# SDRAM_DDR3_4x16.net
KiCad netlist of a schematic drawn in Altium Designer
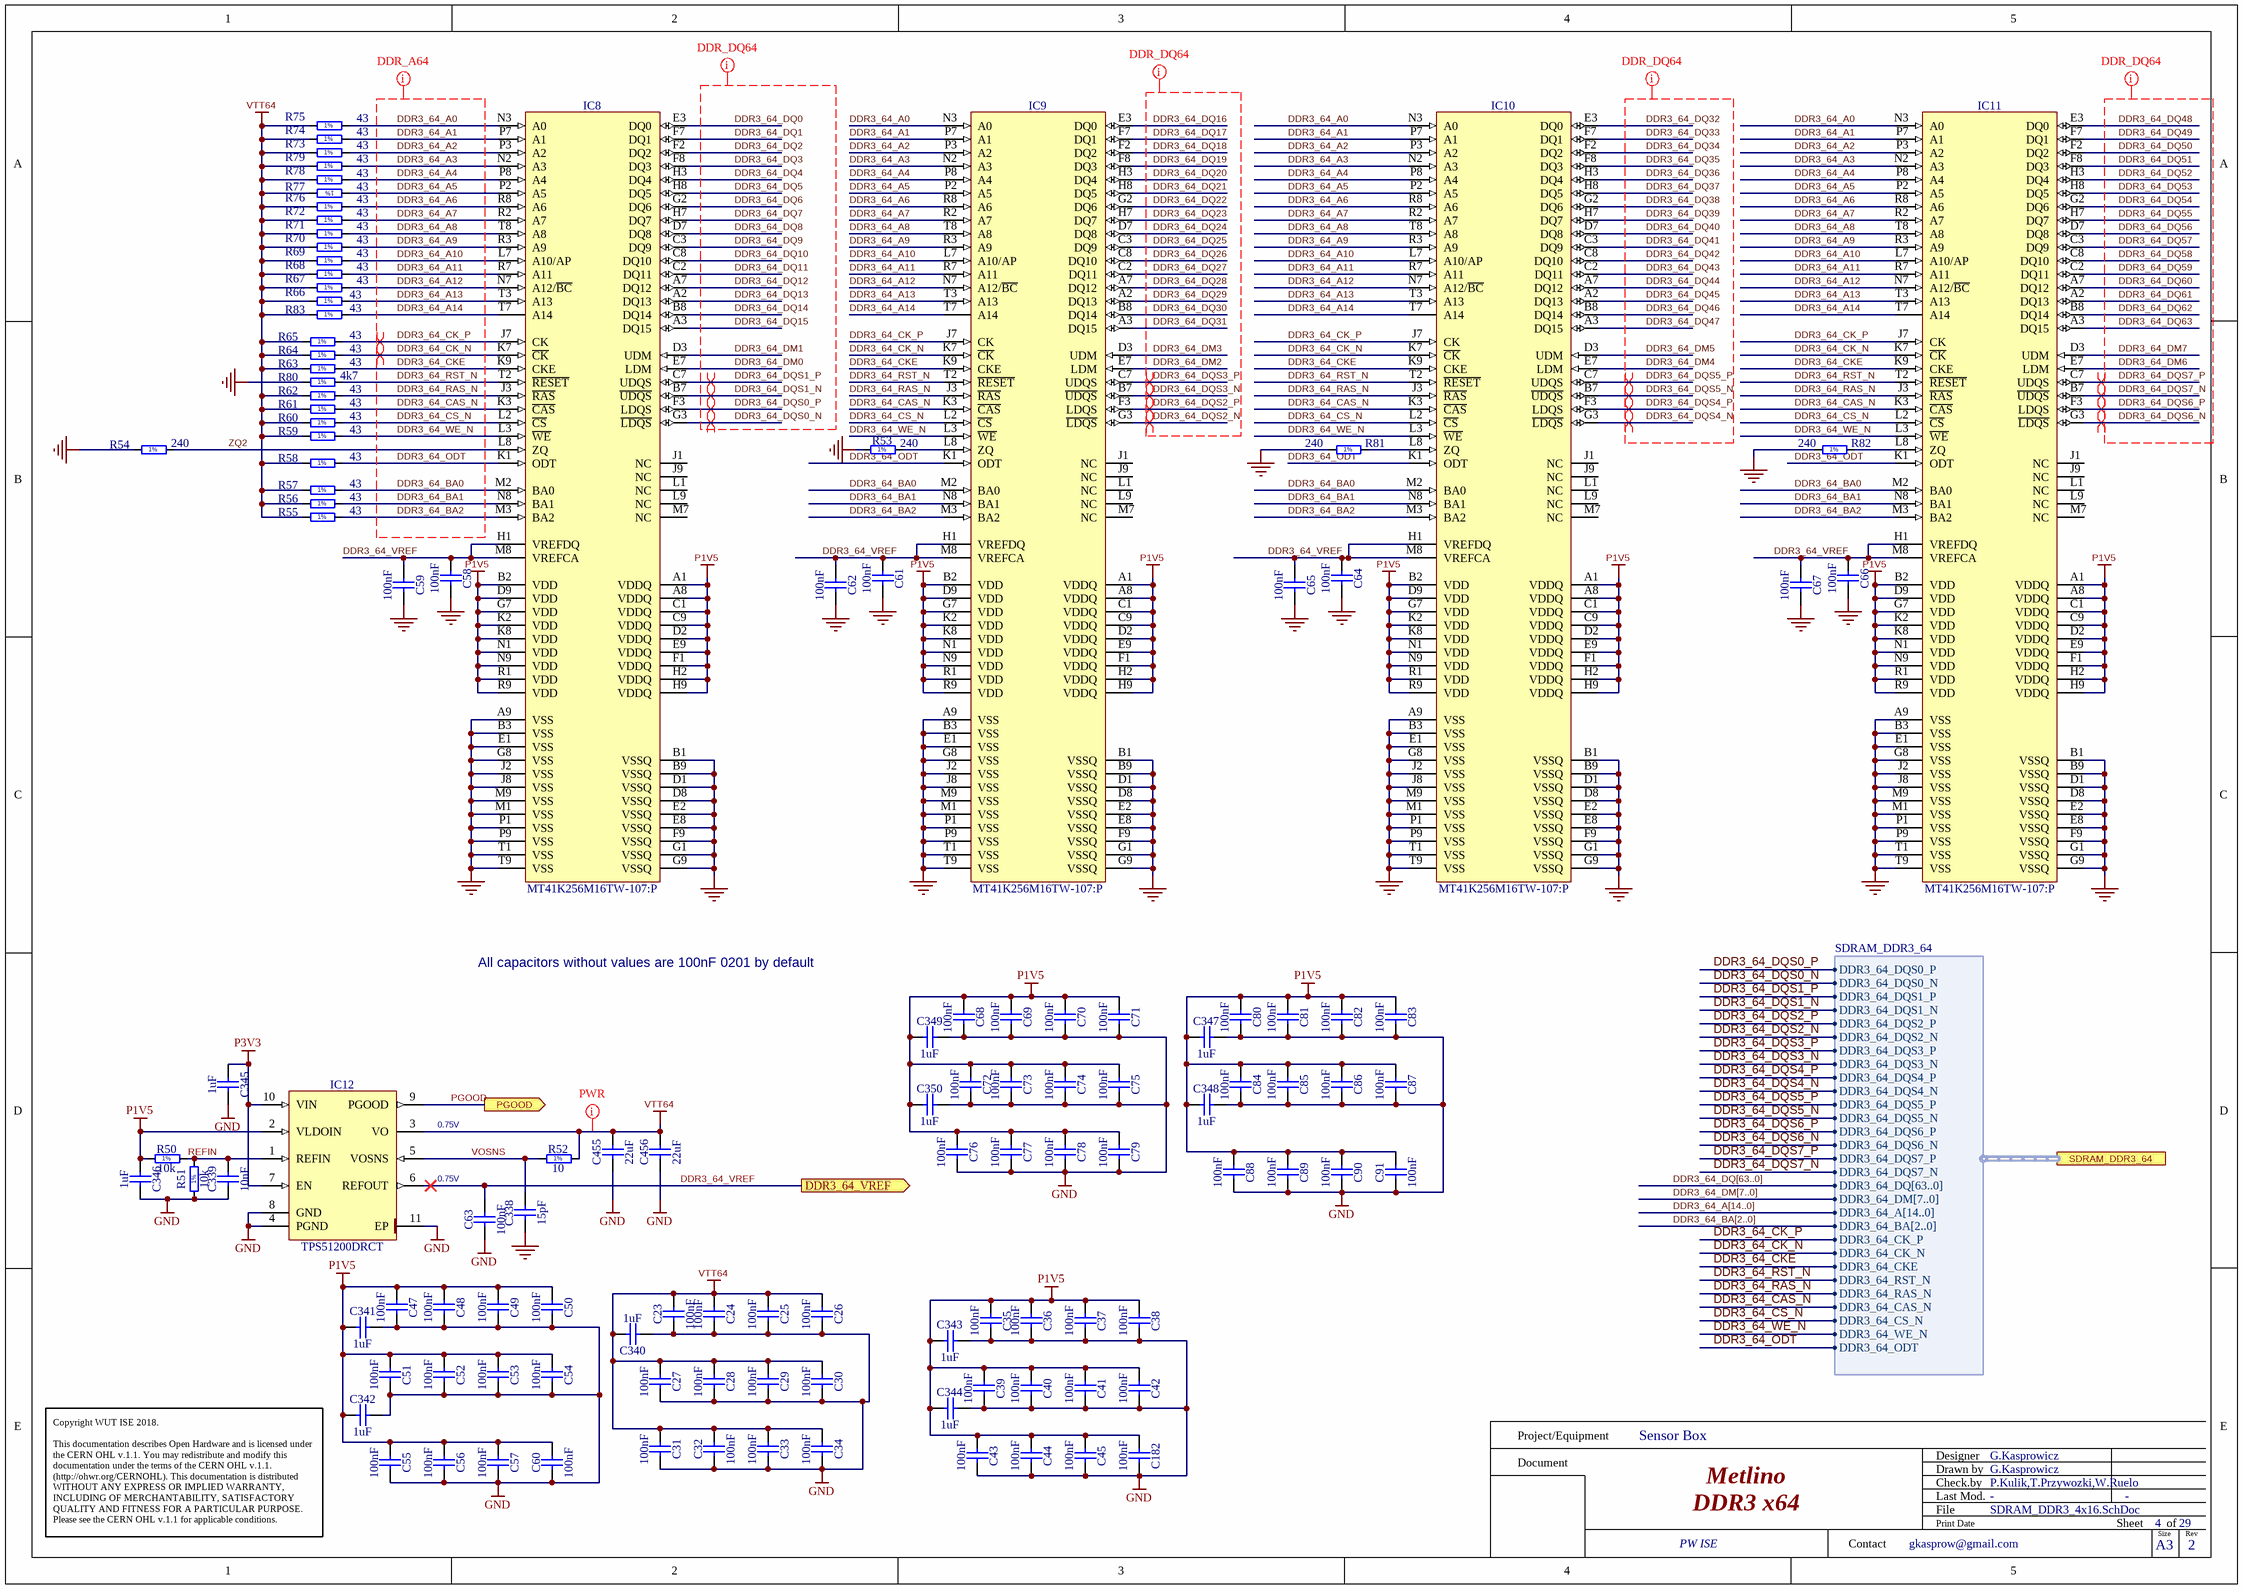
[diagram p0: SDRAM_DDR3_4x16.SchDoc]

(export (version "E")
  (design (tool "Eeschema 10.0.6"))
  (components
    (comp (ref "C23")
      (value "100nF")
      (footprint "CAPC0603X33N")
      (description "Non-polarised capacitor")
      (fields
        (field (name "MANUFACTURER PART NUMBER") "CC0201_100NF_6.3V_10%_X5R")
        (field (name "MANUFACTURER") "GENERIC")
        (field (name "AUTHOR") "CERN DEM JLC")
      )
      (libsource (lib "Capacitors") (part "Capacitor - non polarized"))
    )
    (comp (ref "C24")
      (value "100nF")
      (footprint "CAPC0603X33N")
      (description "Non-polarised capacitor")
      (fields
        (field (name "MANUFACTURER PART NUMBER") "CC0201_100NF_6.3V_10%_X5R")
        (field (name "MANUFACTURER") "GENERIC")
        (field (name "AUTHOR") "CERN DEM JLC")
      )
      (libsource (lib "Capacitors") (part "Capacitor - non polarized"))
    )
    (comp (ref "C25")
      (value "100nF")
      (footprint "CAPC0603X33N")
      (description "Non-polarised capacitor")
      (fields
        (field (name "MANUFACTURER PART NUMBER") "CC0201_100NF_6.3V_10%_X5R")
        (field (name "MANUFACTURER") "GENERIC")
        (field (name "AUTHOR") "CERN DEM JLC")
      )
      (libsource (lib "Capacitors") (part "Capacitor - non polarized"))
    )
    (comp (ref "C26")
      (value "100nF")
      (footprint "CAPC0603X33N")
      (description "Non-polarised capacitor")
      (fields
        (field (name "MANUFACTURER PART NUMBER") "CC0201_100NF_6.3V_10%_X5R")
        (field (name "MANUFACTURER") "GENERIC")
        (field (name "AUTHOR") "CERN DEM JLC")
      )
      (libsource (lib "Capacitors") (part "Capacitor - non polarized"))
    )
    (comp (ref "C27")
      (value "100nF")
      (footprint "CAPC0603X33N")
      (description "Non-polarised capacitor")
      (fields
        (field (name "MANUFACTURER PART NUMBER") "CC0201_100NF_6.3V_10%_X5R")
        (field (name "MANUFACTURER") "GENERIC")
        (field (name "AUTHOR") "CERN DEM JLC")
      )
      (libsource (lib "Capacitors") (part "Capacitor - non polarized"))
    )
    (comp (ref "C28")
      (value "100nF")
      (footprint "CAPC0603X33N")
      (description "Non-polarised capacitor")
      (fields
        (field (name "MANUFACTURER PART NUMBER") "CC0201_100NF_6.3V_10%_X5R")
        (field (name "MANUFACTURER") "GENERIC")
        (field (name "AUTHOR") "CERN DEM JLC")
      )
      (libsource (lib "Capacitors") (part "Capacitor - non polarized"))
    )
    (comp (ref "C29")
      (value "100nF")
      (footprint "CAPC0603X33N")
      (description "Non-polarised capacitor")
      (fields
        (field (name "MANUFACTURER PART NUMBER") "CC0201_100NF_6.3V_10%_X5R")
        (field (name "MANUFACTURER") "GENERIC")
        (field (name "AUTHOR") "CERN DEM JLC")
      )
      (libsource (lib "Capacitors") (part "Capacitor - non polarized"))
    )
    (comp (ref "C30")
      (value "100nF")
      (footprint "CAPC0603X33N")
      (description "Non-polarised capacitor")
      (fields
        (field (name "MANUFACTURER PART NUMBER") "CC0201_100NF_6.3V_10%_X5R")
        (field (name "MANUFACTURER") "GENERIC")
        (field (name "AUTHOR") "CERN DEM JLC")
      )
      (libsource (lib "Capacitors") (part "Capacitor - non polarized"))
    )
    (comp (ref "C31")
      (value "100nF")
      (footprint "CAPC0603X33N")
      (description "Non-polarised capacitor")
      (fields
        (field (name "MANUFACTURER PART NUMBER") "CC0201_100NF_6.3V_10%_X5R")
        (field (name "MANUFACTURER") "GENERIC")
        (field (name "AUTHOR") "CERN DEM JLC")
      )
      (libsource (lib "Capacitors") (part "Capacitor - non polarized"))
    )
    (comp (ref "C32")
      (value "100nF")
      (footprint "CAPC0603X33N")
      (description "Non-polarised capacitor")
      (fields
        (field (name "MANUFACTURER PART NUMBER") "CC0201_100NF_6.3V_10%_X5R")
        (field (name "MANUFACTURER") "GENERIC")
        (field (name "AUTHOR") "CERN DEM JLC")
      )
      (libsource (lib "Capacitors") (part "Capacitor - non polarized"))
    )
    (comp (ref "C33")
      (value "100nF")
      (footprint "CAPC0603X33N")
      (description "Non-polarised capacitor")
      (fields
        (field (name "MANUFACTURER PART NUMBER") "CC0201_100NF_6.3V_10%_X5R")
        (field (name "MANUFACTURER") "GENERIC")
        (field (name "AUTHOR") "CERN DEM JLC")
      )
      (libsource (lib "Capacitors") (part "Capacitor - non polarized"))
    )
    (comp (ref "C34")
      (value "100nF")
      (footprint "CAPC0603X33N")
      (description "Non-polarised capacitor")
      (fields
        (field (name "MANUFACTURER PART NUMBER") "CC0201_100NF_6.3V_10%_X5R")
        (field (name "MANUFACTURER") "GENERIC")
        (field (name "AUTHOR") "CERN DEM JLC")
      )
      (libsource (lib "Capacitors") (part "Capacitor - non polarized"))
    )
    (comp (ref "C35")
      (value "100nF")
      (footprint "CAPC0603X33N")
      (description "Non-polarised capacitor")
      (fields
        (field (name "MANUFACTURER PART NUMBER") "CC0201_100NF_6.3V_10%_X5R")
        (field (name "MANUFACTURER") "GENERIC")
        (field (name "AUTHOR") "CERN DEM JLC")
      )
      (libsource (lib "Capacitors") (part "Capacitor - non polarized"))
    )
    (comp (ref "C36")
      (value "100nF")
      (footprint "CAPC0603X33N")
      (description "Non-polarised capacitor")
      (fields
        (field (name "MANUFACTURER PART NUMBER") "CC0201_100NF_6.3V_10%_X5R")
        (field (name "MANUFACTURER") "GENERIC")
        (field (name "AUTHOR") "CERN DEM JLC")
      )
      (libsource (lib "Capacitors") (part "Capacitor - non polarized"))
    )
    (comp (ref "C37")
      (value "100nF")
      (footprint "CAPC0603X33N")
      (description "Non-polarised capacitor")
      (fields
        (field (name "MANUFACTURER PART NUMBER") "CC0201_100NF_6.3V_10%_X5R")
        (field (name "MANUFACTURER") "GENERIC")
        (field (name "AUTHOR") "CERN DEM JLC")
      )
      (libsource (lib "Capacitors") (part "Capacitor - non polarized"))
    )
    (comp (ref "C38")
      (value "100nF")
      (footprint "CAPC0603X33N")
      (description "Non-polarised capacitor")
      (fields
        (field (name "MANUFACTURER PART NUMBER") "CC0201_100NF_6.3V_10%_X5R")
        (field (name "MANUFACTURER") "GENERIC")
        (field (name "AUTHOR") "CERN DEM JLC")
      )
      (libsource (lib "Capacitors") (part "Capacitor - non polarized"))
    )
    (comp (ref "C39")
      (value "100nF")
      (footprint "CAPC0603X33N")
      (description "Non-polarised capacitor")
      (fields
        (field (name "MANUFACTURER PART NUMBER") "CC0201_100NF_6.3V_10%_X5R")
        (field (name "MANUFACTURER") "GENERIC")
        (field (name "AUTHOR") "CERN DEM JLC")
      )
      (libsource (lib "Capacitors") (part "Capacitor - non polarized"))
    )
    (comp (ref "C40")
      (value "100nF")
      (footprint "CAPC0603X33N")
      (description "Non-polarised capacitor")
      (fields
        (field (name "MANUFACTURER PART NUMBER") "CC0201_100NF_6.3V_10%_X5R")
        (field (name "MANUFACTURER") "GENERIC")
        (field (name "AUTHOR") "CERN DEM JLC")
      )
      (libsource (lib "Capacitors") (part "Capacitor - non polarized"))
    )
    (comp (ref "C41")
      (value "100nF")
      (footprint "CAPC0603X33N")
      (description "Non-polarised capacitor")
      (fields
        (field (name "MANUFACTURER PART NUMBER") "CC0201_100NF_6.3V_10%_X5R")
        (field (name "MANUFACTURER") "GENERIC")
        (field (name "AUTHOR") "CERN DEM JLC")
      )
      (libsource (lib "Capacitors") (part "Capacitor - non polarized"))
    )
    (comp (ref "C42")
      (value "100nF")
      (footprint "CAPC0603X33N")
      (description "Non-polarised capacitor")
      (fields
        (field (name "MANUFACTURER PART NUMBER") "CC0201_100NF_6.3V_10%_X5R")
        (field (name "MANUFACTURER") "GENERIC")
        (field (name "AUTHOR") "CERN DEM JLC")
      )
      (libsource (lib "Capacitors") (part "Capacitor - non polarized"))
    )
    (comp (ref "C43")
      (value "100nF")
      (footprint "CAPC0603X33N")
      (description "Non-polarised capacitor")
      (fields
        (field (name "MANUFACTURER PART NUMBER") "CC0201_100NF_6.3V_10%_X5R")
        (field (name "MANUFACTURER") "GENERIC")
        (field (name "AUTHOR") "CERN DEM JLC")
      )
      (libsource (lib "Capacitors") (part "Capacitor - non polarized"))
    )
    (comp (ref "C44")
      (value "100nF")
      (footprint "CAPC0603X33N")
      (description "Non-polarised capacitor")
      (fields
        (field (name "MANUFACTURER PART NUMBER") "CC0201_100NF_6.3V_10%_X5R")
        (field (name "MANUFACTURER") "GENERIC")
        (field (name "AUTHOR") "CERN DEM JLC")
      )
      (libsource (lib "Capacitors") (part "Capacitor - non polarized"))
    )
    (comp (ref "C45")
      (value "100nF")
      (footprint "CAPC0603X33N")
      (description "Non-polarised capacitor")
      (fields
        (field (name "MANUFACTURER PART NUMBER") "CC0201_100NF_6.3V_10%_X5R")
        (field (name "MANUFACTURER") "GENERIC")
        (field (name "AUTHOR") "CERN DEM JLC")
      )
      (libsource (lib "Capacitors") (part "Capacitor - non polarized"))
    )
    (comp (ref "C47")
      (value "100nF")
      (footprint "CAPC0603X33N")
      (description "Non-polarised capacitor")
      (fields
        (field (name "MANUFACTURER PART NUMBER") "CC0201_100NF_6.3V_10%_X5R")
        (field (name "MANUFACTURER") "GENERIC")
        (field (name "AUTHOR") "CERN DEM JLC")
      )
      (libsource (lib "Capacitors") (part "Capacitor - non polarized"))
    )
    (comp (ref "C48")
      (value "100nF")
      (footprint "CAPC0603X33N")
      (description "Non-polarised capacitor")
      (fields
        (field (name "MANUFACTURER PART NUMBER") "CC0201_100NF_6.3V_10%_X5R")
        (field (name "MANUFACTURER") "GENERIC")
        (field (name "AUTHOR") "CERN DEM JLC")
      )
      (libsource (lib "Capacitors") (part "Capacitor - non polarized"))
    )
    (comp (ref "C49")
      (value "100nF")
      (footprint "CAPC0603X33N")
      (description "Non-polarised capacitor")
      (fields
        (field (name "MANUFACTURER PART NUMBER") "CC0201_100NF_6.3V_10%_X5R")
        (field (name "MANUFACTURER") "GENERIC")
        (field (name "AUTHOR") "CERN DEM JLC")
      )
      (libsource (lib "Capacitors") (part "Capacitor - non polarized"))
    )
    (comp (ref "C50")
      (value "100nF")
      (footprint "CAPC0603X33N")
      (description "Non-polarised capacitor")
      (fields
        (field (name "MANUFACTURER PART NUMBER") "CC0201_100NF_6.3V_10%_X5R")
        (field (name "MANUFACTURER") "GENERIC")
        (field (name "AUTHOR") "CERN DEM JLC")
      )
      (libsource (lib "Capacitors") (part "Capacitor - non polarized"))
    )
    (comp (ref "C51")
      (value "100nF")
      (footprint "CAPC0603X33N")
      (description "Non-polarised capacitor")
      (fields
        (field (name "MANUFACTURER PART NUMBER") "CC0201_100NF_6.3V_10%_X5R")
        (field (name "MANUFACTURER") "GENERIC")
        (field (name "AUTHOR") "CERN DEM JLC")
      )
      (libsource (lib "Capacitors") (part "Capacitor - non polarized"))
    )
    (comp (ref "C52")
      (value "100nF")
      (footprint "CAPC0603X33N")
      (description "Non-polarised capacitor")
      (fields
        (field (name "MANUFACTURER PART NUMBER") "CC0201_100NF_6.3V_10%_X5R")
        (field (name "MANUFACTURER") "GENERIC")
        (field (name "AUTHOR") "CERN DEM JLC")
      )
      (libsource (lib "Capacitors") (part "Capacitor - non polarized"))
    )
    (comp (ref "C53")
      (value "100nF")
      (footprint "CAPC0603X33N")
      (description "Non-polarised capacitor")
      (fields
        (field (name "MANUFACTURER PART NUMBER") "CC0201_100NF_6.3V_10%_X5R")
        (field (name "MANUFACTURER") "GENERIC")
        (field (name "AUTHOR") "CERN DEM JLC")
      )
      (libsource (lib "Capacitors") (part "Capacitor - non polarized"))
    )
    (comp (ref "C54")
      (value "100nF")
      (footprint "CAPC0603X33N")
      (description "Non-polarised capacitor")
      (fields
        (field (name "MANUFACTURER PART NUMBER") "CC0201_100NF_6.3V_10%_X5R")
        (field (name "MANUFACTURER") "GENERIC")
        (field (name "AUTHOR") "CERN DEM JLC")
      )
      (libsource (lib "Capacitors") (part "Capacitor - non polarized"))
    )
    (comp (ref "C55")
      (value "100nF")
      (footprint "CAPC0603X33N")
      (description "Non-polarised capacitor")
      (fields
        (field (name "MANUFACTURER PART NUMBER") "CC0201_100NF_6.3V_10%_X5R")
        (field (name "MANUFACTURER") "GENERIC")
        (field (name "AUTHOR") "CERN DEM JLC")
      )
      (libsource (lib "Capacitors") (part "Capacitor - non polarized"))
    )
    (comp (ref "C56")
      (value "100nF")
      (footprint "CAPC0603X33N")
      (description "Non-polarised capacitor")
      (fields
        (field (name "MANUFACTURER PART NUMBER") "CC0201_100NF_6.3V_10%_X5R")
        (field (name "MANUFACTURER") "GENERIC")
        (field (name "AUTHOR") "CERN DEM JLC")
      )
      (libsource (lib "Capacitors") (part "Capacitor - non polarized"))
    )
    (comp (ref "C57")
      (value "100nF")
      (footprint "CAPC0603X33N")
      (description "Non-polarised capacitor")
      (fields
        (field (name "MANUFACTURER PART NUMBER") "CC0201_100NF_6.3V_10%_X5R")
        (field (name "MANUFACTURER") "GENERIC")
        (field (name "AUTHOR") "CERN DEM JLC")
      )
      (libsource (lib "Capacitors") (part "Capacitor - non polarized"))
    )
    (comp (ref "C58")
      (value "100nF")
      (footprint "CAPC0603X33N")
      (description "Non-polarised capacitor")
      (fields
        (field (name "MANUFACTURER PART NUMBER") "CC0201_100NF_6.3V_10%_X5R")
        (field (name "MANUFACTURER") "GENERIC")
        (field (name "AUTHOR") "CERN DEM JLC")
      )
      (libsource (lib "Capacitors") (part "Capacitor - non polarized"))
    )
    (comp (ref "C59")
      (value "100nF")
      (footprint "CAPC0603X33N")
      (description "Non-polarised capacitor")
      (fields
        (field (name "MANUFACTURER PART NUMBER") "CC0201_100NF_6.3V_10%_X5R")
        (field (name "MANUFACTURER") "GENERIC")
        (field (name "AUTHOR") "CERN DEM JLC")
      )
      (libsource (lib "Capacitors") (part "Capacitor - non polarized"))
    )
    (comp (ref "C60")
      (value "100nF")
      (footprint "CAPC0603X33N")
      (description "Non-polarised capacitor")
      (fields
        (field (name "MANUFACTURER PART NUMBER") "CC0201_100NF_6.3V_10%_X5R")
        (field (name "MANUFACTURER") "GENERIC")
        (field (name "AUTHOR") "CERN DEM JLC")
      )
      (libsource (lib "Capacitors") (part "Capacitor - non polarized"))
    )
    (comp (ref "C61")
      (value "100nF")
      (footprint "CAPC0603X33N")
      (description "Non-polarised capacitor")
      (fields
        (field (name "MANUFACTURER PART NUMBER") "CC0201_100NF_6.3V_10%_X5R")
        (field (name "MANUFACTURER") "GENERIC")
        (field (name "AUTHOR") "CERN DEM JLC")
      )
      (libsource (lib "Capacitors") (part "Capacitor - non polarized"))
    )
    (comp (ref "C62")
      (value "100nF")
      (footprint "CAPC0603X33N")
      (description "Non-polarised capacitor")
      (fields
        (field (name "MANUFACTURER PART NUMBER") "CC0201_100NF_6.3V_10%_X5R")
        (field (name "MANUFACTURER") "GENERIC")
        (field (name "AUTHOR") "CERN DEM JLC")
      )
      (libsource (lib "Capacitors") (part "Capacitor - non polarized"))
    )
    (comp (ref "C63")
      (value "100nF")
      (footprint "CAPC0603X33N")
      (description "Non-polarised capacitor")
      (fields
        (field (name "MANUFACTURER PART NUMBER") "CC0201_100NF_6.3V_10%_X5R")
        (field (name "MANUFACTURER") "GENERIC")
        (field (name "AUTHOR") "CERN DEM JLC")
      )
      (libsource (lib "Capacitors") (part "Capacitor - non polarized"))
    )
    (comp (ref "C64")
      (value "100nF")
      (footprint "CAPC0603X33N")
      (description "Non-polarised capacitor")
      (fields
        (field (name "MANUFACTURER PART NUMBER") "CC0201_100NF_6.3V_10%_X5R")
        (field (name "MANUFACTURER") "GENERIC")
        (field (name "AUTHOR") "CERN DEM JLC")
      )
      (libsource (lib "Capacitors") (part "Capacitor - non polarized"))
    )
    (comp (ref "C65")
      (value "100nF")
      (footprint "CAPC0603X33N")
      (description "Non-polarised capacitor")
      (fields
        (field (name "MANUFACTURER PART NUMBER") "CC0201_100NF_6.3V_10%_X5R")
        (field (name "MANUFACTURER") "GENERIC")
        (field (name "AUTHOR") "CERN DEM JLC")
      )
      (libsource (lib "Capacitors") (part "Capacitor - non polarized"))
    )
    (comp (ref "C66")
      (value "100nF")
      (footprint "CAPC0603X33N")
      (description "Non-polarised capacitor")
      (fields
        (field (name "MANUFACTURER PART NUMBER") "CC0201_100NF_6.3V_10%_X5R")
        (field (name "MANUFACTURER") "GENERIC")
        (field (name "AUTHOR") "CERN DEM JLC")
      )
      (libsource (lib "Capacitors") (part "Capacitor - non polarized"))
    )
    (comp (ref "C67")
      (value "100nF")
      (footprint "CAPC0603X33N")
      (description "Non-polarised capacitor")
      (fields
        (field (name "MANUFACTURER PART NUMBER") "CC0201_100NF_6.3V_10%_X5R")
        (field (name "MANUFACTURER") "GENERIC")
        (field (name "AUTHOR") "CERN DEM JLC")
      )
      (libsource (lib "Capacitors") (part "Capacitor - non polarized"))
    )
    (comp (ref "C68")
      (value "100nF")
      (footprint "CAPC0603X33N")
      (description "Non-polarised capacitor")
      (fields
        (field (name "MANUFACTURER PART NUMBER") "CC0201_100NF_6.3V_10%_X5R")
        (field (name "MANUFACTURER") "GENERIC")
        (field (name "AUTHOR") "CERN DEM JLC")
      )
      (libsource (lib "Capacitors") (part "Capacitor - non polarized"))
    )
    (comp (ref "C69")
      (value "100nF")
      (footprint "CAPC0603X33N")
      (description "Non-polarised capacitor")
      (fields
        (field (name "MANUFACTURER PART NUMBER") "CC0201_100NF_6.3V_10%_X5R")
        (field (name "MANUFACTURER") "GENERIC")
        (field (name "AUTHOR") "CERN DEM JLC")
      )
      (libsource (lib "Capacitors") (part "Capacitor - non polarized"))
    )
    (comp (ref "C70")
      (value "100nF")
      (footprint "CAPC0603X33N")
      (description "Non-polarised capacitor")
      (fields
        (field (name "MANUFACTURER PART NUMBER") "CC0201_100NF_6.3V_10%_X5R")
        (field (name "MANUFACTURER") "GENERIC")
        (field (name "AUTHOR") "CERN DEM JLC")
      )
      (libsource (lib "Capacitors") (part "Capacitor - non polarized"))
    )
    (comp (ref "C71")
      (value "100nF")
      (footprint "CAPC0603X33N")
      (description "Non-polarised capacitor")
      (fields
        (field (name "MANUFACTURER PART NUMBER") "CC0201_100NF_6.3V_10%_X5R")
        (field (name "MANUFACTURER") "GENERIC")
        (field (name "AUTHOR") "CERN DEM JLC")
      )
      (libsource (lib "Capacitors") (part "Capacitor - non polarized"))
    )
    (comp (ref "C72")
      (value "100nF")
      (footprint "CAPC0603X33N")
      (description "Non-polarised capacitor")
      (fields
        (field (name "MANUFACTURER PART NUMBER") "CC0201_100NF_6.3V_10%_X5R")
        (field (name "MANUFACTURER") "GENERIC")
        (field (name "AUTHOR") "CERN DEM JLC")
      )
      (libsource (lib "Capacitors") (part "Capacitor - non polarized"))
    )
    (comp (ref "C73")
      (value "100nF")
      (footprint "CAPC0603X33N")
      (description "Non-polarised capacitor")
      (fields
        (field (name "MANUFACTURER PART NUMBER") "CC0201_100NF_6.3V_10%_X5R")
        (field (name "MANUFACTURER") "GENERIC")
        (field (name "AUTHOR") "CERN DEM JLC")
      )
      (libsource (lib "Capacitors") (part "Capacitor - non polarized"))
    )
    (comp (ref "C74")
      (value "100nF")
      (footprint "CAPC0603X33N")
      (description "Non-polarised capacitor")
      (fields
        (field (name "MANUFACTURER PART NUMBER") "CC0201_100NF_6.3V_10%_X5R")
        (field (name "MANUFACTURER") "GENERIC")
        (field (name "AUTHOR") "CERN DEM JLC")
      )
      (libsource (lib "Capacitors") (part "Capacitor - non polarized"))
    )
    (comp (ref "C75")
      (value "100nF")
      (footprint "CAPC0603X33N")
      (description "Non-polarised capacitor")
      (fields
        (field (name "MANUFACTURER PART NUMBER") "CC0201_100NF_6.3V_10%_X5R")
        (field (name "MANUFACTURER") "GENERIC")
        (field (name "AUTHOR") "CERN DEM JLC")
      )
      (libsource (lib "Capacitors") (part "Capacitor - non polarized"))
    )
    (comp (ref "C76")
      (value "100nF")
      (footprint "CAPC0603X33N")
      (description "Non-polarised capacitor")
      (fields
        (field (name "MANUFACTURER PART NUMBER") "CC0201_100NF_6.3V_10%_X5R")
        (field (name "MANUFACTURER") "GENERIC")
        (field (name "AUTHOR") "CERN DEM JLC")
      )
      (libsource (lib "Capacitors") (part "Capacitor - non polarized"))
    )
    (comp (ref "C77")
      (value "100nF")
      (footprint "CAPC0603X33N")
      (description "Non-polarised capacitor")
      (fields
        (field (name "MANUFACTURER PART NUMBER") "CC0201_100NF_6.3V_10%_X5R")
        (field (name "MANUFACTURER") "GENERIC")
        (field (name "AUTHOR") "CERN DEM JLC")
      )
      (libsource (lib "Capacitors") (part "Capacitor - non polarized"))
    )
    (comp (ref "C78")
      (value "100nF")
      (footprint "CAPC0603X33N")
      (description "Non-polarised capacitor")
      (fields
        (field (name "MANUFACTURER PART NUMBER") "CC0201_100NF_6.3V_10%_X5R")
        (field (name "MANUFACTURER") "GENERIC")
        (field (name "AUTHOR") "CERN DEM JLC")
      )
      (libsource (lib "Capacitors") (part "Capacitor - non polarized"))
    )
    (comp (ref "C79")
      (value "100nF")
      (footprint "CAPC0603X33N")
      (description "Non-polarised capacitor")
      (fields
        (field (name "MANUFACTURER PART NUMBER") "CC0201_100NF_6.3V_10%_X5R")
        (field (name "MANUFACTURER") "GENERIC")
        (field (name "AUTHOR") "CERN DEM JLC")
      )
      (libsource (lib "Capacitors") (part "Capacitor - non polarized"))
    )
    (comp (ref "C80")
      (value "100nF")
      (footprint "CAPC0603X33N")
      (description "Non-polarised capacitor")
      (fields
        (field (name "MANUFACTURER PART NUMBER") "CC0201_100NF_6.3V_10%_X5R")
        (field (name "MANUFACTURER") "GENERIC")
        (field (name "AUTHOR") "CERN DEM JLC")
      )
      (libsource (lib "Capacitors") (part "Capacitor - non polarized"))
    )
    (comp (ref "C81")
      (value "100nF")
      (footprint "CAPC0603X33N")
      (description "Non-polarised capacitor")
      (fields
        (field (name "MANUFACTURER PART NUMBER") "CC0201_100NF_6.3V_10%_X5R")
        (field (name "MANUFACTURER") "GENERIC")
        (field (name "AUTHOR") "CERN DEM JLC")
      )
      (libsource (lib "Capacitors") (part "Capacitor - non polarized"))
    )
    (comp (ref "C82")
      (value "100nF")
      (footprint "CAPC0603X33N")
      (description "Non-polarised capacitor")
      (fields
        (field (name "MANUFACTURER PART NUMBER") "CC0201_100NF_6.3V_10%_X5R")
        (field (name "MANUFACTURER") "GENERIC")
        (field (name "AUTHOR") "CERN DEM JLC")
      )
      (libsource (lib "Capacitors") (part "Capacitor - non polarized"))
    )
    (comp (ref "C83")
      (value "100nF")
      (footprint "CAPC0603X33N")
      (description "Non-polarised capacitor")
      (fields
        (field (name "MANUFACTURER PART NUMBER") "CC0201_100NF_6.3V_10%_X5R")
        (field (name "MANUFACTURER") "GENERIC")
        (field (name "AUTHOR") "CERN DEM JLC")
      )
      (libsource (lib "Capacitors") (part "Capacitor - non polarized"))
    )
    (comp (ref "C84")
      (value "100nF")
      (footprint "CAPC0603X33N")
      (description "Non-polarised capacitor")
      (fields
        (field (name "MANUFACTURER PART NUMBER") "CC0201_100NF_6.3V_10%_X5R")
        (field (name "MANUFACTURER") "GENERIC")
        (field (name "AUTHOR") "CERN DEM JLC")
      )
      (libsource (lib "Capacitors") (part "Capacitor - non polarized"))
    )
    (comp (ref "C85")
      (value "100nF")
      (footprint "CAPC0603X33N")
      (description "Non-polarised capacitor")
      (fields
        (field (name "MANUFACTURER PART NUMBER") "CC0201_100NF_6.3V_10%_X5R")
        (field (name "MANUFACTURER") "GENERIC")
        (field (name "AUTHOR") "CERN DEM JLC")
      )
      (libsource (lib "Capacitors") (part "Capacitor - non polarized"))
    )
    (comp (ref "C86")
      (value "100nF")
      (footprint "CAPC0603X33N")
      (description "Non-polarised capacitor")
      (fields
        (field (name "MANUFACTURER PART NUMBER") "CC0201_100NF_6.3V_10%_X5R")
        (field (name "MANUFACTURER") "GENERIC")
        (field (name "AUTHOR") "CERN DEM JLC")
      )
      (libsource (lib "Capacitors") (part "Capacitor - non polarized"))
    )
    (comp (ref "C87")
      (value "100nF")
      (footprint "CAPC0603X33N")
      (description "Non-polarised capacitor")
      (fields
        (field (name "MANUFACTURER PART NUMBER") "CC0201_100NF_6.3V_10%_X5R")
        (field (name "MANUFACTURER") "GENERIC")
        (field (name "AUTHOR") "CERN DEM JLC")
      )
      (libsource (lib "Capacitors") (part "Capacitor - non polarized"))
    )
    (comp (ref "C88")
      (value "100nF")
      (footprint "CAPC0603X33N")
      (description "Non-polarised capacitor")
      (fields
        (field (name "MANUFACTURER PART NUMBER") "CC0201_100NF_6.3V_10%_X5R")
        (field (name "MANUFACTURER") "GENERIC")
        (field (name "AUTHOR") "CERN DEM JLC")
      )
      (libsource (lib "Capacitors") (part "Capacitor - non polarized"))
    )
    (comp (ref "C89")
      (value "100nF")
      (footprint "CAPC0603X33N")
      (description "Non-polarised capacitor")
      (fields
        (field (name "MANUFACTURER PART NUMBER") "CC0201_100NF_6.3V_10%_X5R")
        (field (name "MANUFACTURER") "GENERIC")
        (field (name "AUTHOR") "CERN DEM JLC")
      )
      (libsource (lib "Capacitors") (part "Capacitor - non polarized"))
    )
    (comp (ref "C90")
      (value "100nF")
      (footprint "CAPC0603X33N")
      (description "Non-polarised capacitor")
      (fields
        (field (name "MANUFACTURER PART NUMBER") "CC0201_100NF_6.3V_10%_X5R")
        (field (name "MANUFACTURER") "GENERIC")
        (field (name "AUTHOR") "CERN DEM JLC")
      )
      (libsource (lib "Capacitors") (part "Capacitor - non polarized"))
    )
    (comp (ref "C91")
      (value "100nF")
      (footprint "CAPC0603X33N")
      (description "Non-polarised capacitor")
      (fields
        (field (name "MANUFACTURER PART NUMBER") "CC0201_100NF_6.3V_10%_X5R")
        (field (name "MANUFACTURER") "GENERIC")
        (field (name "AUTHOR") "CERN DEM JLC")
      )
      (libsource (lib "Capacitors") (part "Capacitor - non polarized"))
    )
    (comp (ref "C182")
      (value "100nF")
      (footprint "CAPC0603X33N")
      (description "Non-polarised capacitor")
      (fields
        (field (name "MANUFACTURER PART NUMBER") "CC0201_100NF_6.3V_10%_X5R")
        (field (name "MANUFACTURER") "GENERIC")
        (field (name "AUTHOR") "CERN DEM JLC")
      )
      (libsource (lib "Capacitors") (part "Capacitor - non polarized"))
    )
    (comp (ref "C338")
      (value "15pF")
      (footprint "CAPC1005X55N")
      (description "Non-polarised capacitor")
      (fields
        (field (name "MANUFACTURER PART NUMBER") "CC0402_15PF_50V_5%_C0G")
        (field (name "MANUFACTURER") "GENERIC")
        (field (name "AUTHOR") "CERN DEM JLC")
      )
      (libsource (lib "Capacitors") (part "Capacitor - non polarized"))
    )
    (comp (ref "C339")
      (value "10nF")
      (footprint "CAPC1005X55N")
      (description "Non-polarised capacitor")
      (fields
        (field (name "MANUFACTURER PART NUMBER") "CC0402_10NF_25V_10%_X7R")
        (field (name "MANUFACTURER") "GENERIC")
        (field (name "AUTHOR") "CERN DEM JLC")
      )
      (libsource (lib "Capacitors") (part "Capacitor - non polarized"))
    )
    (comp (ref "C340")
      (value "1uF")
      (footprint "CAPC1005X55N")
      (description "Non-polarised capacitor")
      (fields
        (field (name "MANUFACTURER PART NUMBER") "CC0402_1UF_16V_10%_X5R")
        (field (name "MANUFACTURER") "GENERIC")
        (field (name "AUTHOR") "CERN DEM JLC")
      )
      (libsource (lib "Capacitors") (part "Capacitor - non polarized"))
    )
    (comp (ref "C341")
      (value "1uF")
      (footprint "CAPC1005X55N")
      (description "Non-polarised capacitor")
      (fields
        (field (name "MANUFACTURER PART NUMBER") "CC0402_1UF_16V_10%_X5R")
        (field (name "MANUFACTURER") "GENERIC")
        (field (name "AUTHOR") "CERN DEM JLC")
      )
      (libsource (lib "Capacitors") (part "Capacitor - non polarized"))
    )
    (comp (ref "C342")
      (value "1uF")
      (footprint "CAPC1005X55N")
      (description "Non-polarised capacitor")
      (fields
        (field (name "MANUFACTURER PART NUMBER") "CC0402_1UF_16V_10%_X5R")
        (field (name "MANUFACTURER") "GENERIC")
        (field (name "AUTHOR") "CERN DEM JLC")
      )
      (libsource (lib "Capacitors") (part "Capacitor - non polarized"))
    )
    (comp (ref "C343")
      (value "1uF")
      (footprint "CAPC1005X55N")
      (description "Non-polarised capacitor")
      (fields
        (field (name "MANUFACTURER PART NUMBER") "CC0402_1UF_16V_10%_X5R")
        (field (name "MANUFACTURER") "GENERIC")
        (field (name "AUTHOR") "CERN DEM JLC")
      )
      (libsource (lib "Capacitors") (part "Capacitor - non polarized"))
    )
    (comp (ref "C344")
      (value "1uF")
      (footprint "CAPC1005X55N")
      (description "Non-polarised capacitor")
      (fields
        (field (name "MANUFACTURER PART NUMBER") "CC0402_1UF_16V_10%_X5R")
        (field (name "MANUFACTURER") "GENERIC")
        (field (name "AUTHOR") "CERN DEM JLC")
      )
      (libsource (lib "Capacitors") (part "Capacitor - non polarized"))
    )
    (comp (ref "C345")
      (value "1uF")
      (footprint "CAPC1005X55N")
      (description "Non-polarised capacitor")
      (fields
        (field (name "MANUFACTURER PART NUMBER") "CC0402_1UF_16V_10%_X5R")
        (field (name "MANUFACTURER") "GENERIC")
        (field (name "AUTHOR") "CERN DEM JLC")
      )
      (libsource (lib "Capacitors") (part "Capacitor - non polarized"))
    )
    (comp (ref "C346")
      (value "1uF")
      (footprint "CAPC1005X55N")
      (description "Non-polarised capacitor")
      (fields
        (field (name "MANUFACTURER PART NUMBER") "CC0402_1UF_16V_10%_X5R")
        (field (name "MANUFACTURER") "GENERIC")
        (field (name "AUTHOR") "CERN DEM JLC")
      )
      (libsource (lib "Capacitors") (part "Capacitor - non polarized"))
    )
    (comp (ref "C347")
      (value "1uF")
      (footprint "CAPC1005X55N")
      (description "Non-polarised capacitor")
      (fields
        (field (name "MANUFACTURER PART NUMBER") "CC0402_1UF_16V_10%_X5R")
        (field (name "MANUFACTURER") "GENERIC")
        (field (name "AUTHOR") "CERN DEM JLC")
      )
      (libsource (lib "Capacitors") (part "Capacitor - non polarized"))
    )
    (comp (ref "C348")
      (value "1uF")
      (footprint "CAPC1005X55N")
      (description "Non-polarised capacitor")
      (fields
        (field (name "MANUFACTURER PART NUMBER") "CC0402_1UF_16V_10%_X5R")
        (field (name "MANUFACTURER") "GENERIC")
        (field (name "AUTHOR") "CERN DEM JLC")
      )
      (libsource (lib "Capacitors") (part "Capacitor - non polarized"))
    )
    (comp (ref "C349")
      (value "1uF")
      (footprint "CAPC1005X55N")
      (description "Non-polarised capacitor")
      (fields
        (field (name "MANUFACTURER PART NUMBER") "CC0402_1UF_16V_10%_X5R")
        (field (name "MANUFACTURER") "GENERIC")
        (field (name "AUTHOR") "CERN DEM JLC")
      )
      (libsource (lib "Capacitors") (part "Capacitor - non polarized"))
    )
    (comp (ref "C350")
      (value "1uF")
      (footprint "CAPC1005X55N")
      (description "Non-polarised capacitor")
      (fields
        (field (name "MANUFACTURER PART NUMBER") "CC0402_1UF_16V_10%_X5R")
        (field (name "MANUFACTURER") "GENERIC")
        (field (name "AUTHOR") "CERN DEM JLC")
      )
      (libsource (lib "Capacitors") (part "Capacitor - non polarized"))
    )
    (comp (ref "C455")
      (value "22uF")
      (footprint "CAPC2012X135N")
      (description "Non-polarised capacitor")
      (fields
        (field (name "MANUFACTURER PART NUMBER") "CC0805_22UF_10V_+80%-20%_Y5V")
        (field (name "MANUFACTURER") "GENERIC")
        (field (name "AUTHOR") "CERN DEM JLC")
      )
      (libsource (lib "Capacitors") (part "Capacitor - non polarized"))
    )
    (comp (ref "C456")
      (value "22uF")
      (footprint "CAPC2012X135N")
      (description "Non-polarised capacitor")
      (fields
        (field (name "MANUFACTURER PART NUMBER") "CC0805_22UF_10V_+80%-20%_Y5V")
        (field (name "MANUFACTURER") "GENERIC")
        (field (name "AUTHOR") "CERN DEM JLC")
      )
      (libsource (lib "Capacitors") (part "Capacitor - non polarized"))
    )
    (comp (ref "IC8")
      (value "MT41K256M16TW-107:P")
      (footprint "BGA96C80P9X16_800X1400X120")
      (description "32 Meg x 16 x 8 Banks DDR3L SDRAM")
      (fields (field (name "MANUFACTURER") "MICRON TECHNOLOGY") (field (name "AUTHOR") "CERN DEM MR"))
      (libsource (lib "ICs And Semiconductors") (part "MT41K256M16TW-107{colon}P"))
    )
    (comp (ref "IC9")
      (value "MT41K256M16TW-107:P")
      (footprint "BGA96C80P9X16_800X1400X120")
      (description "32 Meg x 16 x 8 Banks DDR3L SDRAM")
      (fields (field (name "MANUFACTURER") "MICRON TECHNOLOGY") (field (name "AUTHOR") "CERN DEM MR"))
      (libsource (lib "ICs And Semiconductors") (part "MT41K256M16TW-107{colon}P"))
    )
    (comp (ref "IC10")
      (value "MT41K256M16TW-107:P")
      (footprint "BGA96C80P9X16_800X1400X120")
      (description "32 Meg x 16 x 8 Banks DDR3L SDRAM")
      (fields (field (name "MANUFACTURER") "MICRON TECHNOLOGY") (field (name "AUTHOR") "CERN DEM MR"))
      (libsource (lib "ICs And Semiconductors") (part "MT41K256M16TW-107{colon}P"))
    )
    (comp (ref "IC11")
      (value "MT41K256M16TW-107:P")
      (footprint "BGA96C80P9X16_800X1400X120")
      (description "32 Meg x 16 x 8 Banks DDR3L SDRAM")
      (fields (field (name "MANUFACTURER") "MICRON TECHNOLOGY") (field (name "AUTHOR") "CERN DEM MR"))
      (libsource (lib "ICs And Semiconductors") (part "MT41K256M16TW-107{colon}P"))
    )
    (comp (ref "IC12")
      (value "TPS51200DRCT")
      (footprint "TEXAS_DRC (S-PVSON-N10)")
      (description "Sink/Source DDR Termination Regulator")
      (fields (field (name "MANUFACTURER") "TEXAS INSTRUMENTS") (field (name "AUTHOR") "CERN DEM JLC"))
      (libsource (lib "ICs And Semiconductors") (part "TPS51200DRC"))
    )
    (comp (ref "R50")
      (value "10k")
      (footprint "RESC1005X40N")
      (description "Resistor - 1%")
      (fields
        (field (name "MANUFACTURER PART NUMBER") "R0402_10K_1%_0.0625W_100PPM")
        (field (name "MANUFACTURER") "GENERIC")
        (field (name "AUTHOR") "CERN DEM JLC")
      )
      (libsource (lib "Resistors") (part "Resistor - 1%"))
    )
    (comp (ref "R51")
      (value "10k")
      (footprint "RESC1005X40N")
      (description "Resistor - 1%")
      (fields
        (field (name "MANUFACTURER PART NUMBER") "R0402_10K_1%_0.0625W_100PPM")
        (field (name "MANUFACTURER") "GENERIC")
        (field (name "AUTHOR") "CERN DEM JLC")
      )
      (libsource (lib "Resistors") (part "Resistor - 1%"))
    )
    (comp (ref "R52")
      (value "10")
      (footprint "RESC1005X40N")
      (description "Resistor - 1%")
      (fields
        (field (name "MANUFACTURER PART NUMBER") "R0402_10R_1%_0.0625W_200PPM")
        (field (name "MANUFACTURER") "GENERIC")
        (field (name "AUTHOR") "CERN DEM JLC")
      )
      (libsource (lib "Resistors") (part "Resistor - 1%"))
    )
    (comp (ref "R53")
      (value "240")
      (footprint "RESC1005X40N")
      (description "Resistor - 1%")
      (fields
        (field (name "MANUFACTURER PART NUMBER") "R0402_240R_1%_0.0625W_100PPM")
        (field (name "MANUFACTURER") "GENERIC")
        (field (name "AUTHOR") "CERN DEM JLC")
      )
      (libsource (lib "Resistors") (part "Resistor - 1%"))
    )
    (comp (ref "R54")
      (value "240")
      (footprint "RESC1005X40N")
      (description "Resistor - 1%")
      (fields
        (field (name "MANUFACTURER PART NUMBER") "R0402_240R_1%_0.0625W_100PPM")
        (field (name "MANUFACTURER") "GENERIC")
        (field (name "AUTHOR") "CERN DEM JLC")
      )
      (libsource (lib "Resistors") (part "Resistor - 1%"))
    )
    (comp (ref "R55")
      (value "43")
      (footprint "RESC1005X40N")
      (description "Resistor - 1%")
      (fields
        (field (name "MANUFACTURER PART NUMBER") "R0402_43R_1%_0.0625W_100PPM")
        (field (name "MANUFACTURER") "GENERIC")
        (field (name "AUTHOR") "CERN DEM JLC")
      )
      (libsource (lib "Resistors") (part "Resistor - 1%"))
    )
    (comp (ref "R56")
      (value "43")
      (footprint "RESC1005X40N")
      (description "Resistor - 1%")
      (fields
        (field (name "MANUFACTURER PART NUMBER") "R0402_43R_1%_0.0625W_100PPM")
        (field (name "MANUFACTURER") "GENERIC")
        (field (name "AUTHOR") "CERN DEM JLC")
      )
      (libsource (lib "Resistors") (part "Resistor - 1%"))
    )
    (comp (ref "R57")
      (value "43")
      (footprint "RESC1005X40N")
      (description "Resistor - 1%")
      (fields
        (field (name "MANUFACTURER PART NUMBER") "R0402_43R_1%_0.0625W_100PPM")
        (field (name "MANUFACTURER") "GENERIC")
        (field (name "AUTHOR") "CERN DEM JLC")
      )
      (libsource (lib "Resistors") (part "Resistor - 1%"))
    )
    (comp (ref "R58")
      (value "43")
      (footprint "RESC1005X40N")
      (description "Resistor - 1%")
      (fields
        (field (name "MANUFACTURER PART NUMBER") "R0402_43R_1%_0.0625W_100PPM")
        (field (name "MANUFACTURER") "GENERIC")
        (field (name "AUTHOR") "CERN DEM JLC")
      )
      (libsource (lib "Resistors") (part "Resistor - 1%"))
    )
    (comp (ref "R59")
      (value "43")
      (footprint "RESC1005X40N")
      (description "Resistor - 1%")
      (fields
        (field (name "MANUFACTURER PART NUMBER") "R0402_43R_1%_0.0625W_100PPM")
        (field (name "MANUFACTURER") "GENERIC")
        (field (name "AUTHOR") "CERN DEM JLC")
      )
      (libsource (lib "Resistors") (part "Resistor - 1%"))
    )
    (comp (ref "R60")
      (value "43")
      (footprint "RESC1005X40N")
      (description "Resistor - 1%")
      (fields
        (field (name "MANUFACTURER PART NUMBER") "R0402_43R_1%_0.0625W_100PPM")
        (field (name "MANUFACTURER") "GENERIC")
        (field (name "AUTHOR") "CERN DEM JLC")
      )
      (libsource (lib "Resistors") (part "Resistor - 1%"))
    )
    (comp (ref "R61")
      (value "43")
      (footprint "RESC1005X40N")
      (description "Resistor - 1%")
      (fields
        (field (name "MANUFACTURER PART NUMBER") "R0402_43R_1%_0.0625W_100PPM")
        (field (name "MANUFACTURER") "GENERIC")
        (field (name "AUTHOR") "CERN DEM JLC")
      )
      (libsource (lib "Resistors") (part "Resistor - 1%"))
    )
    (comp (ref "R62")
      (value "43")
      (footprint "RESC1005X40N")
      (description "Resistor - 1%")
      (fields
        (field (name "MANUFACTURER PART NUMBER") "R0402_43R_1%_0.0625W_100PPM")
        (field (name "MANUFACTURER") "GENERIC")
        (field (name "AUTHOR") "CERN DEM JLC")
      )
      (libsource (lib "Resistors") (part "Resistor - 1%"))
    )
    (comp (ref "R63")
      (value "43")
      (footprint "RESC1005X40N")
      (description "Resistor - 1%")
      (fields
        (field (name "MANUFACTURER PART NUMBER") "R0402_43R_1%_0.0625W_100PPM")
        (field (name "MANUFACTURER") "GENERIC")
        (field (name "AUTHOR") "CERN DEM JLC")
      )
      (libsource (lib "Resistors") (part "Resistor - 1%"))
    )
    (comp (ref "R64")
      (value "43")
      (footprint "RESC1005X40N")
      (description "Resistor - 1%")
      (fields
        (field (name "MANUFACTURER PART NUMBER") "R0402_43R_1%_0.0625W_100PPM")
        (field (name "MANUFACTURER") "GENERIC")
        (field (name "AUTHOR") "CERN DEM JLC")
      )
      (libsource (lib "Resistors") (part "Resistor - 1%"))
    )
    (comp (ref "R65")
      (value "43")
      (footprint "RESC1005X40N")
      (description "Resistor - 1%")
      (fields
        (field (name "MANUFACTURER PART NUMBER") "R0402_43R_1%_0.0625W_100PPM")
        (field (name "MANUFACTURER") "GENERIC")
        (field (name "AUTHOR") "CERN DEM JLC")
      )
      (libsource (lib "Resistors") (part "Resistor - 1%"))
    )
    (comp (ref "R66")
      (value "43")
      (footprint "RESC1005X40N")
      (description "Resistor - 1%")
      (fields
        (field (name "MANUFACTURER PART NUMBER") "R0402_43R_1%_0.0625W_100PPM")
        (field (name "MANUFACTURER") "GENERIC")
        (field (name "AUTHOR") "CERN DEM JLC")
      )
      (libsource (lib "Resistors") (part "Resistor - 1%"))
    )
    (comp (ref "R67")
      (value "43")
      (footprint "RESC1005X40N")
      (description "Resistor - 1%")
      (fields
        (field (name "MANUFACTURER PART NUMBER") "R0402_43R_1%_0.0625W_100PPM")
        (field (name "MANUFACTURER") "GENERIC")
        (field (name "AUTHOR") "CERN DEM JLC")
      )
      (libsource (lib "Resistors") (part "Resistor - 1%"))
    )
    (comp (ref "R68")
      (value "43")
      (footprint "RESC1005X40N")
      (description "Resistor - 1%")
      (fields
        (field (name "MANUFACTURER PART NUMBER") "R0402_43R_1%_0.0625W_100PPM")
        (field (name "MANUFACTURER") "GENERIC")
        (field (name "AUTHOR") "CERN DEM JLC")
      )
      (libsource (lib "Resistors") (part "Resistor - 1%"))
    )
    (comp (ref "R69")
      (value "43")
      (footprint "RESC1005X40N")
      (description "Resistor - 1%")
      (fields
        (field (name "MANUFACTURER PART NUMBER") "R0402_43R_1%_0.0625W_100PPM")
        (field (name "MANUFACTURER") "GENERIC")
        (field (name "AUTHOR") "CERN DEM JLC")
      )
      (libsource (lib "Resistors") (part "Resistor - 1%"))
    )
    (comp (ref "R70")
      (value "43")
      (footprint "RESC1005X40N")
      (description "Resistor - 1%")
      (fields
        (field (name "MANUFACTURER PART NUMBER") "R0402_43R_1%_0.0625W_100PPM")
        (field (name "MANUFACTURER") "GENERIC")
        (field (name "AUTHOR") "CERN DEM JLC")
      )
      (libsource (lib "Resistors") (part "Resistor - 1%"))
    )
    (comp (ref "R71")
      (value "43")
      (footprint "RESC1005X40N")
      (description "Resistor - 1%")
      (fields
        (field (name "MANUFACTURER PART NUMBER") "R0402_43R_1%_0.0625W_100PPM")
        (field (name "MANUFACTURER") "GENERIC")
        (field (name "AUTHOR") "CERN DEM JLC")
      )
      (libsource (lib "Resistors") (part "Resistor - 1%"))
    )
    (comp (ref "R72")
      (value "43")
      (footprint "RESC1005X40N")
      (description "Resistor - 1%")
      (fields
        (field (name "MANUFACTURER PART NUMBER") "R0402_43R_1%_0.0625W_100PPM")
        (field (name "MANUFACTURER") "GENERIC")
        (field (name "AUTHOR") "CERN DEM JLC")
      )
      (libsource (lib "Resistors") (part "Resistor - 1%"))
    )
    (comp (ref "R73")
      (value "43")
      (footprint "RESC1005X40N")
      (description "Resistor - 1%")
      (fields
        (field (name "MANUFACTURER PART NUMBER") "R0402_43R_1%_0.0625W_100PPM")
        (field (name "MANUFACTURER") "GENERIC")
        (field (name "AUTHOR") "CERN DEM JLC")
      )
      (libsource (lib "Resistors") (part "Resistor - 1%"))
    )
    (comp (ref "R74")
      (value "43")
      (footprint "RESC1005X40N")
      (description "Resistor - 1%")
      (fields
        (field (name "MANUFACTURER PART NUMBER") "R0402_43R_1%_0.0625W_100PPM")
        (field (name "MANUFACTURER") "GENERIC")
        (field (name "AUTHOR") "CERN DEM JLC")
      )
      (libsource (lib "Resistors") (part "Resistor - 1%"))
    )
    (comp (ref "R75")
      (value "43")
      (footprint "RESC1005X40N")
      (description "Resistor - 1%")
      (fields
        (field (name "MANUFACTURER PART NUMBER") "R0402_43R_1%_0.0625W_100PPM")
        (field (name "MANUFACTURER") "GENERIC")
        (field (name "AUTHOR") "CERN DEM JLC")
      )
      (libsource (lib "Resistors") (part "Resistor - 1%"))
    )
    (comp (ref "R76")
      (value "43")
      (footprint "RESC1005X40N")
      (description "Resistor - 1%")
      (fields
        (field (name "MANUFACTURER PART NUMBER") "R0402_43R_1%_0.0625W_100PPM")
        (field (name "MANUFACTURER") "GENERIC")
        (field (name "AUTHOR") "CERN DEM JLC")
      )
      (libsource (lib "Resistors") (part "Resistor - 1%"))
    )
    (comp (ref "R77")
      (value "43")
      (footprint "RESC1005X40N")
      (description "Resistor - 1%")
      (fields
        (field (name "MANUFACTURER PART NUMBER") "R0402_43R_1%_0.0625W_100PPM")
        (field (name "MANUFACTURER") "GENERIC")
        (field (name "AUTHOR") "CERN DEM JLC")
      )
      (libsource (lib "Resistors") (part "Resistor - 1%"))
    )
    (comp (ref "R78")
      (value "43")
      (footprint "RESC1005X40N")
      (description "Resistor - 1%")
      (fields
        (field (name "MANUFACTURER PART NUMBER") "R0402_43R_1%_0.0625W_100PPM")
        (field (name "MANUFACTURER") "GENERIC")
        (field (name "AUTHOR") "CERN DEM JLC")
      )
      (libsource (lib "Resistors") (part "Resistor - 1%"))
    )
    (comp (ref "R79")
      (value "43")
      (footprint "RESC1005X40N")
      (description "Resistor - 1%")
      (fields
        (field (name "MANUFACTURER PART NUMBER") "R0402_43R_1%_0.0625W_100PPM")
        (field (name "MANUFACTURER") "GENERIC")
        (field (name "AUTHOR") "CERN DEM JLC")
      )
      (libsource (lib "Resistors") (part "Resistor - 1%"))
    )
    (comp (ref "R80")
      (value "4k7")
      (footprint "RESC1005X40N")
      (description "Resistor - 1%")
      (fields
        (field (name "MANUFACTURER PART NUMBER") "R0402_4K7_1%_0.0625W_100PPM")
        (field (name "MANUFACTURER") "GENERIC")
        (field (name "AUTHOR") "CERN DEM JLC")
      )
      (libsource (lib "Resistors") (part "Resistor - 1%"))
    )
    (comp (ref "R81")
      (value "240")
      (footprint "RESC1005X40N")
      (description "Resistor - 1%")
      (fields
        (field (name "MANUFACTURER PART NUMBER") "R0402_240R_1%_0.0625W_100PPM")
        (field (name "MANUFACTURER") "GENERIC")
        (field (name "AUTHOR") "CERN DEM JLC")
      )
      (libsource (lib "Resistors") (part "Resistor - 1%"))
    )
    (comp (ref "R82")
      (value "240")
      (footprint "RESC1005X40N")
      (description "Resistor - 1%")
      (fields
        (field (name "MANUFACTURER PART NUMBER") "R0402_240R_1%_0.0625W_100PPM")
        (field (name "MANUFACTURER") "GENERIC")
        (field (name "AUTHOR") "CERN DEM JLC")
      )
      (libsource (lib "Resistors") (part "Resistor - 1%"))
    )
    (comp (ref "R83")
      (value "43")
      (footprint "RESC1005X40N")
      (description "Resistor - 1%")
      (fields
        (field (name "MANUFACTURER PART NUMBER") "R0402_43R_1%_0.0625W_100PPM")
        (field (name "MANUFACTURER") "GENERIC")
        (field (name "AUTHOR") "CERN DEM JLC")
      )
      (libsource (lib "Resistors") (part "Resistor - 1%"))
    )
  )
  (nets
    (net (code "2") (name "/DDR3_64_A0") (class "Default")
      (node (ref "IC10") (pin "N3") (pinfunction "A0_N3") (pintype "input"))
      (node (ref "IC11") (pin "N3") (pinfunction "A0_N3") (pintype "input"))
      (node (ref "IC8") (pin "N3") (pinfunction "A0_N3") (pintype "input"))
      (node (ref "IC9") (pin "N3") (pinfunction "A0_N3") (pintype "input"))
      (node (ref "R75") (pin "2") (pinfunction "2_2") (pintype "passive"))
    )
    (net (code "3") (name "/DDR3_64_A1") (class "Default")
      (node (ref "IC10") (pin "P7") (pinfunction "A1_P7") (pintype "input"))
      (node (ref "IC11") (pin "P7") (pinfunction "A1_P7") (pintype "input"))
      (node (ref "IC8") (pin "P7") (pinfunction "A1_P7") (pintype "input"))
      (node (ref "IC9") (pin "P7") (pinfunction "A1_P7") (pintype "input"))
      (node (ref "R74") (pin "2") (pinfunction "2_2") (pintype "passive"))
    )
    (net (code "4") (name "/DDR3_64_A2") (class "Default")
      (node (ref "IC10") (pin "P3") (pinfunction "A2_P3") (pintype "input"))
      (node (ref "IC11") (pin "P3") (pinfunction "A2_P3") (pintype "input"))
      (node (ref "IC8") (pin "P3") (pinfunction "A2_P3") (pintype "input"))
      (node (ref "IC9") (pin "P3") (pinfunction "A2_P3") (pintype "input"))
      (node (ref "R73") (pin "2") (pinfunction "2_2") (pintype "passive"))
    )
    (net (code "5") (name "/DDR3_64_A3") (class "Default")
      (node (ref "IC10") (pin "N2") (pinfunction "A3_N2") (pintype "input"))
      (node (ref "IC11") (pin "N2") (pinfunction "A3_N2") (pintype "input"))
      (node (ref "IC8") (pin "N2") (pinfunction "A3_N2") (pintype "input"))
      (node (ref "IC9") (pin "N2") (pinfunction "A3_N2") (pintype "input"))
      (node (ref "R79") (pin "2") (pinfunction "2_2") (pintype "passive"))
    )
    (net (code "6") (name "/DDR3_64_A4") (class "Default")
      (node (ref "IC10") (pin "P8") (pinfunction "A4_P8") (pintype "input"))
      (node (ref "IC11") (pin "P8") (pinfunction "A4_P8") (pintype "input"))
      (node (ref "IC8") (pin "P8") (pinfunction "A4_P8") (pintype "input"))
      (node (ref "IC9") (pin "P8") (pinfunction "A4_P8") (pintype "input"))
      (node (ref "R78") (pin "2") (pinfunction "2_2") (pintype "passive"))
    )
    (net (code "7") (name "/DDR3_64_A5") (class "Default")
      (node (ref "IC10") (pin "P2") (pinfunction "A5_P2") (pintype "input"))
      (node (ref "IC11") (pin "P2") (pinfunction "A5_P2") (pintype "input"))
      (node (ref "IC8") (pin "P2") (pinfunction "A5_P2") (pintype "input"))
      (node (ref "IC9") (pin "P2") (pinfunction "A5_P2") (pintype "input"))
      (node (ref "R77") (pin "2") (pinfunction "2_2") (pintype "passive"))
    )
    (net (code "8") (name "/DDR3_64_A6") (class "Default")
      (node (ref "IC10") (pin "R8") (pinfunction "A6_R8") (pintype "input"))
      (node (ref "IC11") (pin "R8") (pinfunction "A6_R8") (pintype "input"))
      (node (ref "IC8") (pin "R8") (pinfunction "A6_R8") (pintype "input"))
      (node (ref "IC9") (pin "R8") (pinfunction "A6_R8") (pintype "input"))
      (node (ref "R76") (pin "2") (pinfunction "2_2") (pintype "passive"))
    )
    (net (code "9") (name "/DDR3_64_A7") (class "Default")
      (node (ref "IC10") (pin "R2") (pinfunction "A7_R2") (pintype "input"))
      (node (ref "IC11") (pin "R2") (pinfunction "A7_R2") (pintype "input"))
      (node (ref "IC8") (pin "R2") (pinfunction "A7_R2") (pintype "input"))
      (node (ref "IC9") (pin "R2") (pinfunction "A7_R2") (pintype "input"))
      (node (ref "R72") (pin "2") (pinfunction "2_2") (pintype "passive"))
    )
    (net (code "10") (name "/DDR3_64_A8") (class "Default")
      (node (ref "IC10") (pin "T8") (pinfunction "A8_T8") (pintype "input"))
      (node (ref "IC11") (pin "T8") (pinfunction "A8_T8") (pintype "input"))
      (node (ref "IC8") (pin "T8") (pinfunction "A8_T8") (pintype "input"))
      (node (ref "IC9") (pin "T8") (pinfunction "A8_T8") (pintype "input"))
      (node (ref "R71") (pin "2") (pinfunction "2_2") (pintype "passive"))
    )
    (net (code "11") (name "/DDR3_64_A9") (class "Default")
      (node (ref "IC10") (pin "R3") (pinfunction "A9_R3") (pintype "input"))
      (node (ref "IC11") (pin "R3") (pinfunction "A9_R3") (pintype "input"))
      (node (ref "IC8") (pin "R3") (pinfunction "A9_R3") (pintype "input"))
      (node (ref "IC9") (pin "R3") (pinfunction "A9_R3") (pintype "input"))
      (node (ref "R70") (pin "2") (pinfunction "2_2") (pintype "passive"))
    )
    (net (code "12") (name "/DDR3_64_A10") (class "Default")
      (node (ref "IC10") (pin "L7") (pinfunction "A10/AP_L7") (pintype "input"))
      (node (ref "IC11") (pin "L7") (pinfunction "A10/AP_L7") (pintype "input"))
      (node (ref "IC8") (pin "L7") (pinfunction "A10/AP_L7") (pintype "input"))
      (node (ref "IC9") (pin "L7") (pinfunction "A10/AP_L7") (pintype "input"))
      (node (ref "R69") (pin "2") (pinfunction "2_2") (pintype "passive"))
    )
    (net (code "13") (name "/DDR3_64_A11") (class "Default")
      (node (ref "IC10") (pin "R7") (pinfunction "A11_R7") (pintype "input"))
      (node (ref "IC11") (pin "R7") (pinfunction "A11_R7") (pintype "input"))
      (node (ref "IC8") (pin "R7") (pinfunction "A11_R7") (pintype "input"))
      (node (ref "IC9") (pin "R7") (pinfunction "A11_R7") (pintype "input"))
      (node (ref "R68") (pin "2") (pinfunction "2_2") (pintype "passive"))
    )
    (net (code "14") (name "/DDR3_64_A12") (class "Default")
      (node (ref "IC10") (pin "N7") (pinfunction "A12/~{BC}_N7") (pintype "input"))
      (node (ref "IC11") (pin "N7") (pinfunction "A12/~{BC}_N7") (pintype "input"))
      (node (ref "IC8") (pin "N7") (pinfunction "A12/~{BC}_N7") (pintype "input"))
      (node (ref "IC9") (pin "N7") (pinfunction "A12/~{BC}_N7") (pintype "input"))
      (node (ref "R67") (pin "2") (pinfunction "2_2") (pintype "passive"))
    )
    (net (code "15") (name "/DDR3_64_A13") (class "Default")
      (node (ref "IC10") (pin "T3") (pinfunction "A13_T3") (pintype "input"))
      (node (ref "IC11") (pin "T3") (pinfunction "A13_T3") (pintype "input"))
      (node (ref "IC8") (pin "T3") (pinfunction "A13_T3") (pintype "input"))
      (node (ref "IC9") (pin "T3") (pinfunction "A13_T3") (pintype "input"))
      (node (ref "R66") (pin "2") (pinfunction "2_2") (pintype "passive"))
    )
    (net (code "16") (name "/DDR3_64_A14") (class "Default")
      (node (ref "IC10") (pin "T7") (pinfunction "A14_T7") (pintype "passive"))
      (node (ref "IC11") (pin "T7") (pinfunction "A14_T7") (pintype "passive"))
      (node (ref "IC8") (pin "T7") (pinfunction "A14_T7") (pintype "passive"))
      (node (ref "IC9") (pin "T7") (pinfunction "A14_T7") (pintype "passive"))
      (node (ref "R83") (pin "2") (pinfunction "2_2") (pintype "passive"))
    )
    (net (code "18") (name "/DDR3_64_BA0") (class "Default")
      (node (ref "IC10") (pin "M2") (pinfunction "BA0_M2") (pintype "input"))
      (node (ref "IC11") (pin "M2") (pinfunction "BA0_M2") (pintype "input"))
      (node (ref "IC8") (pin "M2") (pinfunction "BA0_M2") (pintype "input"))
      (node (ref "IC9") (pin "M2") (pinfunction "BA0_M2") (pintype "input"))
      (node (ref "R57") (pin "2") (pinfunction "2_2") (pintype "passive"))
    )
    (net (code "19") (name "/DDR3_64_BA1") (class "Default")
      (node (ref "IC10") (pin "N8") (pinfunction "BA1_N8") (pintype "input"))
      (node (ref "IC11") (pin "N8") (pinfunction "BA1_N8") (pintype "input"))
      (node (ref "IC8") (pin "N8") (pinfunction "BA1_N8") (pintype "input"))
      (node (ref "IC9") (pin "N8") (pinfunction "BA1_N8") (pintype "input"))
      (node (ref "R56") (pin "2") (pinfunction "2_2") (pintype "passive"))
    )
    (net (code "20") (name "/DDR3_64_BA2") (class "Default")
      (node (ref "IC10") (pin "M3") (pinfunction "BA2_M3") (pintype "input"))
      (node (ref "IC11") (pin "M3") (pinfunction "BA2_M3") (pintype "input"))
      (node (ref "IC8") (pin "M3") (pinfunction "BA2_M3") (pintype "input"))
      (node (ref "IC9") (pin "M3") (pinfunction "BA2_M3") (pintype "input"))
      (node (ref "R55") (pin "2") (pinfunction "2_2") (pintype "passive"))
    )
    (net (code "21") (name "/DDR3_64_CAS_N") (class "Default")
      (node (ref "IC10") (pin "K3") (pinfunction "~{CAS}_K3") (pintype "input"))
      (node (ref "IC11") (pin "K3") (pinfunction "~{CAS}_K3") (pintype "input"))
      (node (ref "IC8") (pin "K3") (pinfunction "~{CAS}_K3") (pintype "input"))
      (node (ref "IC9") (pin "K3") (pinfunction "~{CAS}_K3") (pintype "input"))
      (node (ref "R61") (pin "2") (pinfunction "2_2") (pintype "passive"))
    )
    (net (code "22") (name "/DDR3_64_CKE") (class "Default")
      (node (ref "IC10") (pin "K9") (pinfunction "CKE_K9") (pintype "input"))
      (node (ref "IC11") (pin "K9") (pinfunction "CKE_K9") (pintype "input"))
      (node (ref "IC8") (pin "K9") (pinfunction "CKE_K9") (pintype "input"))
      (node (ref "IC9") (pin "K9") (pinfunction "CKE_K9") (pintype "input"))
      (node (ref "R63") (pin "2") (pinfunction "2_2") (pintype "passive"))
    )
    (net (code "23") (name "/DDR3_64_CK_N") (class "Default")
      (node (ref "IC10") (pin "K7") (pinfunction "~{CK}_K7") (pintype "input"))
      (node (ref "IC11") (pin "K7") (pinfunction "~{CK}_K7") (pintype "input"))
      (node (ref "IC8") (pin "K7") (pinfunction "~{CK}_K7") (pintype "input"))
      (node (ref "IC9") (pin "K7") (pinfunction "~{CK}_K7") (pintype "input"))
      (node (ref "R64") (pin "2") (pinfunction "2_2") (pintype "passive"))
    )
    (net (code "24") (name "/DDR3_64_CK_P") (class "Default")
      (node (ref "IC10") (pin "J7") (pinfunction "CK_J7") (pintype "input"))
      (node (ref "IC11") (pin "J7") (pinfunction "CK_J7") (pintype "input"))
      (node (ref "IC8") (pin "J7") (pinfunction "CK_J7") (pintype "input"))
      (node (ref "IC9") (pin "J7") (pinfunction "CK_J7") (pintype "input"))
      (node (ref "R65") (pin "2") (pinfunction "2_2") (pintype "passive"))
    )
    (net (code "25") (name "/DDR3_64_CS_N") (class "Default")
      (node (ref "IC10") (pin "L2") (pinfunction "~{CS}_L2") (pintype "input"))
      (node (ref "IC11") (pin "L2") (pinfunction "~{CS}_L2") (pintype "input"))
      (node (ref "IC8") (pin "L2") (pinfunction "~{CS}_L2") (pintype "input"))
      (node (ref "IC9") (pin "L2") (pinfunction "~{CS}_L2") (pintype "input"))
      (node (ref "R60") (pin "2") (pinfunction "2_2") (pintype "passive"))
    )
    (net (code "26") (name "/DDR3_64_DM0") (class "Default")
      (node (ref "IC8") (pin "E7") (pinfunction "LDM_E7") (pintype "input"))
    )
    (net (code "27") (name "/DDR3_64_DM1") (class "Default")
      (node (ref "IC8") (pin "D3") (pinfunction "UDM_D3") (pintype "input"))
    )
    (net (code "28") (name "/DDR3_64_DM2") (class "Default")
      (node (ref "IC9") (pin "E7") (pinfunction "LDM_E7") (pintype "input"))
    )
    (net (code "29") (name "/DDR3_64_DM3") (class "Default")
      (node (ref "IC9") (pin "D3") (pinfunction "UDM_D3") (pintype "input"))
    )
    (net (code "30") (name "/DDR3_64_DM4") (class "Default")
      (node (ref "IC10") (pin "E7") (pinfunction "LDM_E7") (pintype "input"))
    )
    (net (code "31") (name "/DDR3_64_DM5") (class "Default")
      (node (ref "IC10") (pin "D3") (pinfunction "UDM_D3") (pintype "input"))
    )
    (net (code "32") (name "/DDR3_64_DM6") (class "Default")
      (node (ref "IC11") (pin "E7") (pinfunction "LDM_E7") (pintype "input"))
    )
    (net (code "33") (name "/DDR3_64_DM7") (class "Default")
      (node (ref "IC11") (pin "D3") (pinfunction "UDM_D3") (pintype "input"))
    )
    (net (code "35") (name "/DDR3_64_DQ0") (class "Default")
      (node (ref "IC8") (pin "E3") (pinfunction "DQ0_E3") (pintype "bidirectional"))
    )
    (net (code "36") (name "/DDR3_64_DQ1") (class "Default")
      (node (ref "IC8") (pin "F7") (pinfunction "DQ1_F7") (pintype "bidirectional"))
    )
    (net (code "37") (name "/DDR3_64_DQ2") (class "Default")
      (node (ref "IC8") (pin "F2") (pinfunction "DQ2_F2") (pintype "bidirectional"))
    )
    (net (code "38") (name "/DDR3_64_DQ3") (class "Default")
      (node (ref "IC8") (pin "F8") (pinfunction "DQ3_F8") (pintype "bidirectional"))
    )
    (net (code "39") (name "/DDR3_64_DQ4") (class "Default")
      (node (ref "IC8") (pin "H3") (pinfunction "DQ4_H3") (pintype "bidirectional"))
    )
    (net (code "40") (name "/DDR3_64_DQ5") (class "Default")
      (node (ref "IC8") (pin "H8") (pinfunction "DQ5_H8") (pintype "bidirectional"))
    )
    (net (code "41") (name "/DDR3_64_DQ6") (class "Default")
      (node (ref "IC8") (pin "G2") (pinfunction "DQ6_G2") (pintype "bidirectional"))
    )
    (net (code "42") (name "/DDR3_64_DQ7") (class "Default")
      (node (ref "IC8") (pin "H7") (pinfunction "DQ7_H7") (pintype "bidirectional"))
    )
    (net (code "43") (name "/DDR3_64_DQ8") (class "Default")
      (node (ref "IC8") (pin "D7") (pinfunction "DQ8_D7") (pintype "bidirectional"))
    )
    (net (code "44") (name "/DDR3_64_DQ9") (class "Default")
      (node (ref "IC8") (pin "C3") (pinfunction "DQ9_C3") (pintype "bidirectional"))
    )
    (net (code "45") (name "/DDR3_64_DQ10") (class "Default")
      (node (ref "IC8") (pin "C8") (pinfunction "DQ10_C8") (pintype "bidirectional"))
    )
    (net (code "46") (name "/DDR3_64_DQ11") (class "Default")
      (node (ref "IC8") (pin "C2") (pinfunction "DQ11_C2") (pintype "bidirectional"))
    )
    (net (code "47") (name "/DDR3_64_DQ12") (class "Default")
      (node (ref "IC8") (pin "A7") (pinfunction "DQ12_A7") (pintype "bidirectional"))
    )
    (net (code "48") (name "/DDR3_64_DQ13") (class "Default")
      (node (ref "IC8") (pin "A2") (pinfunction "DQ13_A2") (pintype "bidirectional"))
    )
    (net (code "49") (name "/DDR3_64_DQ14") (class "Default")
      (node (ref "IC8") (pin "B8") (pinfunction "DQ14_B8") (pintype "bidirectional"))
    )
    (net (code "50") (name "/DDR3_64_DQ15") (class "Default")
      (node (ref "IC8") (pin "A3") (pinfunction "DQ15_A3") (pintype "bidirectional"))
    )
    (net (code "51") (name "/DDR3_64_DQ16") (class "Default")
      (node (ref "IC9") (pin "E3") (pinfunction "DQ0_E3") (pintype "bidirectional"))
    )
    (net (code "52") (name "/DDR3_64_DQ17") (class "Default")
      (node (ref "IC9") (pin "F7") (pinfunction "DQ1_F7") (pintype "bidirectional"))
    )
    (net (code "53") (name "/DDR3_64_DQ18") (class "Default")
      (node (ref "IC9") (pin "F2") (pinfunction "DQ2_F2") (pintype "bidirectional"))
    )
    (net (code "54") (name "/DDR3_64_DQ19") (class "Default")
      (node (ref "IC9") (pin "F8") (pinfunction "DQ3_F8") (pintype "bidirectional"))
    )
    (net (code "55") (name "/DDR3_64_DQ20") (class "Default")
      (node (ref "IC9") (pin "H3") (pinfunction "DQ4_H3") (pintype "bidirectional"))
    )
    (net (code "56") (name "/DDR3_64_DQ21") (class "Default")
      (node (ref "IC9") (pin "H8") (pinfunction "DQ5_H8") (pintype "bidirectional"))
    )
    (net (code "57") (name "/DDR3_64_DQ22") (class "Default")
      (node (ref "IC9") (pin "G2") (pinfunction "DQ6_G2") (pintype "bidirectional"))
    )
    (net (code "58") (name "/DDR3_64_DQ23") (class "Default")
      (node (ref "IC9") (pin "H7") (pinfunction "DQ7_H7") (pintype "bidirectional"))
    )
    (net (code "59") (name "/DDR3_64_DQ24") (class "Default")
      (node (ref "IC9") (pin "D7") (pinfunction "DQ8_D7") (pintype "bidirectional"))
    )
    (net (code "60") (name "/DDR3_64_DQ25") (class "Default")
      (node (ref "IC9") (pin "C3") (pinfunction "DQ9_C3") (pintype "bidirectional"))
    )
    (net (code "61") (name "/DDR3_64_DQ26") (class "Default")
      (node (ref "IC9") (pin "C8") (pinfunction "DQ10_C8") (pintype "bidirectional"))
    )
    (net (code "62") (name "/DDR3_64_DQ27") (class "Default")
      (node (ref "IC9") (pin "C2") (pinfunction "DQ11_C2") (pintype "bidirectional"))
    )
    (net (code "63") (name "/DDR3_64_DQ28") (class "Default")
      (node (ref "IC9") (pin "A7") (pinfunction "DQ12_A7") (pintype "bidirectional"))
    )
    (net (code "64") (name "/DDR3_64_DQ29") (class "Default")
      (node (ref "IC9") (pin "A2") (pinfunction "DQ13_A2") (pintype "bidirectional"))
    )
    (net (code "65") (name "/DDR3_64_DQ30") (class "Default")
      (node (ref "IC9") (pin "B8") (pinfunction "DQ14_B8") (pintype "bidirectional"))
    )
    (net (code "66") (name "/DDR3_64_DQ31") (class "Default")
      (node (ref "IC9") (pin "A3") (pinfunction "DQ15_A3") (pintype "bidirectional"))
    )
    (net (code "67") (name "/DDR3_64_DQ32") (class "Default")
      (node (ref "IC10") (pin "E3") (pinfunction "DQ0_E3") (pintype "bidirectional"))
    )
    (net (code "68") (name "/DDR3_64_DQ33") (class "Default")
      (node (ref "IC10") (pin "F7") (pinfunction "DQ1_F7") (pintype "bidirectional"))
    )
    (net (code "69") (name "/DDR3_64_DQ34") (class "Default")
      (node (ref "IC10") (pin "F2") (pinfunction "DQ2_F2") (pintype "bidirectional"))
    )
    (net (code "70") (name "/DDR3_64_DQ35") (class "Default")
      (node (ref "IC10") (pin "F8") (pinfunction "DQ3_F8") (pintype "bidirectional"))
    )
    (net (code "71") (name "/DDR3_64_DQ36") (class "Default")
      (node (ref "IC10") (pin "H3") (pinfunction "DQ4_H3") (pintype "bidirectional"))
    )
    (net (code "72") (name "/DDR3_64_DQ37") (class "Default")
      (node (ref "IC10") (pin "H8") (pinfunction "DQ5_H8") (pintype "bidirectional"))
    )
    (net (code "73") (name "/DDR3_64_DQ38") (class "Default")
      (node (ref "IC10") (pin "G2") (pinfunction "DQ6_G2") (pintype "bidirectional"))
    )
    (net (code "74") (name "/DDR3_64_DQ39") (class "Default")
      (node (ref "IC10") (pin "H7") (pinfunction "DQ7_H7") (pintype "bidirectional"))
    )
    (net (code "75") (name "/DDR3_64_DQ40") (class "Default")
      (node (ref "IC10") (pin "D7") (pinfunction "DQ8_D7") (pintype "bidirectional"))
    )
    (net (code "76") (name "/DDR3_64_DQ41") (class "Default")
      (node (ref "IC10") (pin "C3") (pinfunction "DQ9_C3") (pintype "bidirectional"))
    )
    (net (code "77") (name "/DDR3_64_DQ42") (class "Default")
      (node (ref "IC10") (pin "C8") (pinfunction "DQ10_C8") (pintype "bidirectional"))
    )
    (net (code "78") (name "/DDR3_64_DQ43") (class "Default")
      (node (ref "IC10") (pin "C2") (pinfunction "DQ11_C2") (pintype "bidirectional"))
    )
    (net (code "79") (name "/DDR3_64_DQ44") (class "Default")
      (node (ref "IC10") (pin "A7") (pinfunction "DQ12_A7") (pintype "bidirectional"))
    )
    (net (code "80") (name "/DDR3_64_DQ45") (class "Default")
      (node (ref "IC10") (pin "A2") (pinfunction "DQ13_A2") (pintype "bidirectional"))
    )
    (net (code "81") (name "/DDR3_64_DQ46") (class "Default")
      (node (ref "IC10") (pin "B8") (pinfunction "DQ14_B8") (pintype "bidirectional"))
    )
    (net (code "82") (name "/DDR3_64_DQ47") (class "Default")
      (node (ref "IC10") (pin "A3") (pinfunction "DQ15_A3") (pintype "bidirectional"))
    )
    (net (code "83") (name "/DDR3_64_DQ48") (class "Default")
      (node (ref "IC11") (pin "E3") (pinfunction "DQ0_E3") (pintype "bidirectional"))
    )
    (net (code "84") (name "/DDR3_64_DQ49") (class "Default")
      (node (ref "IC11") (pin "F7") (pinfunction "DQ1_F7") (pintype "bidirectional"))
    )
    (net (code "85") (name "/DDR3_64_DQ50") (class "Default")
      (node (ref "IC11") (pin "F2") (pinfunction "DQ2_F2") (pintype "bidirectional"))
    )
    (net (code "86") (name "/DDR3_64_DQ51") (class "Default")
      (node (ref "IC11") (pin "F8") (pinfunction "DQ3_F8") (pintype "bidirectional"))
    )
    (net (code "87") (name "/DDR3_64_DQ52") (class "Default")
      (node (ref "IC11") (pin "H3") (pinfunction "DQ4_H3") (pintype "bidirectional"))
    )
    (net (code "88") (name "/DDR3_64_DQ53") (class "Default")
      (node (ref "IC11") (pin "H8") (pinfunction "DQ5_H8") (pintype "bidirectional"))
    )
    (net (code "89") (name "/DDR3_64_DQ54") (class "Default")
      (node (ref "IC11") (pin "G2") (pinfunction "DQ6_G2") (pintype "bidirectional"))
    )
    (net (code "90") (name "/DDR3_64_DQ55") (class "Default")
      (node (ref "IC11") (pin "H7") (pinfunction "DQ7_H7") (pintype "bidirectional"))
    )
    (net (code "91") (name "/DDR3_64_DQ56") (class "Default")
      (node (ref "IC11") (pin "D7") (pinfunction "DQ8_D7") (pintype "bidirectional"))
    )
    (net (code "92") (name "/DDR3_64_DQ57") (class "Default")
      (node (ref "IC11") (pin "C3") (pinfunction "DQ9_C3") (pintype "bidirectional"))
    )
    (net (code "93") (name "/DDR3_64_DQ58") (class "Default")
      (node (ref "IC11") (pin "C8") (pinfunction "DQ10_C8") (pintype "bidirectional"))
    )
    (net (code "94") (name "/DDR3_64_DQ59") (class "Default")
      (node (ref "IC11") (pin "C2") (pinfunction "DQ11_C2") (pintype "bidirectional"))
    )
    (net (code "95") (name "/DDR3_64_DQ60") (class "Default")
      (node (ref "IC11") (pin "A7") (pinfunction "DQ12_A7") (pintype "bidirectional"))
    )
    (net (code "96") (name "/DDR3_64_DQ61") (class "Default")
      (node (ref "IC11") (pin "A2") (pinfunction "DQ13_A2") (pintype "bidirectional"))
    )
    (net (code "97") (name "/DDR3_64_DQ62") (class "Default")
      (node (ref "IC11") (pin "B8") (pinfunction "DQ14_B8") (pintype "bidirectional"))
    )
    (net (code "98") (name "/DDR3_64_DQ63") (class "Default")
      (node (ref "IC11") (pin "A3") (pinfunction "DQ15_A3") (pintype "bidirectional"))
    )
    (net (code "99") (name "/DDR3_64_DQS0_N") (class "Default")
      (node (ref "IC8") (pin "G3") (pinfunction "~{LDQS}_G3") (pintype "bidirectional"))
    )
    (net (code "100") (name "/DDR3_64_DQS0_P") (class "Default")
      (node (ref "IC8") (pin "F3") (pinfunction "LDQS_F3") (pintype "bidirectional"))
    )
    (net (code "101") (name "/DDR3_64_DQS1_N") (class "Default")
      (node (ref "IC8") (pin "B7") (pinfunction "~{UDQS}_B7") (pintype "bidirectional"))
    )
    (net (code "102") (name "/DDR3_64_DQS1_P") (class "Default")
      (node (ref "IC8") (pin "C7") (pinfunction "UDQS_C7") (pintype "bidirectional"))
    )
    (net (code "103") (name "/DDR3_64_DQS2_N") (class "Default")
      (node (ref "IC9") (pin "G3") (pinfunction "~{LDQS}_G3") (pintype "bidirectional"))
    )
    (net (code "104") (name "/DDR3_64_DQS2_P") (class "Default")
      (node (ref "IC9") (pin "F3") (pinfunction "LDQS_F3") (pintype "bidirectional"))
    )
    (net (code "105") (name "/DDR3_64_DQS3_N") (class "Default")
      (node (ref "IC9") (pin "B7") (pinfunction "~{UDQS}_B7") (pintype "bidirectional"))
    )
    (net (code "106") (name "/DDR3_64_DQS3_P") (class "Default")
      (node (ref "IC9") (pin "C7") (pinfunction "UDQS_C7") (pintype "bidirectional"))
    )
    (net (code "107") (name "/DDR3_64_DQS4_N") (class "Default")
      (node (ref "IC10") (pin "G3") (pinfunction "~{LDQS}_G3") (pintype "bidirectional"))
    )
    (net (code "108") (name "/DDR3_64_DQS4_P") (class "Default")
      (node (ref "IC10") (pin "F3") (pinfunction "LDQS_F3") (pintype "bidirectional"))
    )
    (net (code "109") (name "/DDR3_64_DQS5_N") (class "Default")
      (node (ref "IC10") (pin "B7") (pinfunction "~{UDQS}_B7") (pintype "bidirectional"))
    )
    (net (code "110") (name "/DDR3_64_DQS5_P") (class "Default")
      (node (ref "IC10") (pin "C7") (pinfunction "UDQS_C7") (pintype "bidirectional"))
    )
    (net (code "111") (name "/DDR3_64_DQS6_N") (class "Default")
      (node (ref "IC11") (pin "G3") (pinfunction "~{LDQS}_G3") (pintype "bidirectional"))
    )
    (net (code "112") (name "/DDR3_64_DQS6_P") (class "Default")
      (node (ref "IC11") (pin "F3") (pinfunction "LDQS_F3") (pintype "bidirectional"))
    )
    (net (code "113") (name "/DDR3_64_DQS7_N") (class "Default")
      (node (ref "IC11") (pin "B7") (pinfunction "~{UDQS}_B7") (pintype "bidirectional"))
    )
    (net (code "114") (name "/DDR3_64_DQS7_P") (class "Default")
      (node (ref "IC11") (pin "C7") (pinfunction "UDQS_C7") (pintype "bidirectional"))
    )
    (net (code "116") (name "/DDR3_64_ODT") (class "Default")
      (node (ref "IC10") (pin "K1") (pinfunction "ODT_K1") (pintype "input"))
      (node (ref "IC11") (pin "K1") (pinfunction "ODT_K1") (pintype "input"))
      (node (ref "IC8") (pin "K1") (pinfunction "ODT_K1") (pintype "input"))
      (node (ref "IC9") (pin "K1") (pinfunction "ODT_K1") (pintype "input"))
      (node (ref "R58") (pin "2") (pinfunction "2_2") (pintype "passive"))
    )
    (net (code "117") (name "/DDR3_64_RAS_N") (class "Default")
      (node (ref "IC10") (pin "J3") (pinfunction "~{RAS}_J3") (pintype "input"))
      (node (ref "IC11") (pin "J3") (pinfunction "~{RAS}_J3") (pintype "input"))
      (node (ref "IC8") (pin "J3") (pinfunction "~{RAS}_J3") (pintype "input"))
      (node (ref "IC9") (pin "J3") (pinfunction "~{RAS}_J3") (pintype "input"))
      (node (ref "R62") (pin "2") (pinfunction "2_2") (pintype "passive"))
    )
    (net (code "118") (name "/DDR3_64_RST_N") (class "Default")
      (node (ref "IC10") (pin "T2") (pinfunction "~{RESET}_T2") (pintype "input"))
      (node (ref "IC11") (pin "T2") (pinfunction "~{RESET}_T2") (pintype "input"))
      (node (ref "IC8") (pin "T2") (pinfunction "~{RESET}_T2") (pintype "input"))
      (node (ref "IC9") (pin "T2") (pinfunction "~{RESET}_T2") (pintype "input"))
      (node (ref "R80") (pin "2") (pinfunction "2_2") (pintype "passive"))
    )
    (net (code "119") (name "/DDR3_64_VREF") (class "Default")
      (node (ref "C58") (pin "1") (pinfunction "1_1") (pintype "passive"))
      (node (ref "C59") (pin "1") (pinfunction "1_1") (pintype "passive"))
      (node (ref "C61") (pin "1") (pinfunction "1_1") (pintype "passive"))
      (node (ref "C62") (pin "1") (pinfunction "1_1") (pintype "passive"))
      (node (ref "C63") (pin "2") (pinfunction "2_2") (pintype "passive"))
      (node (ref "C64") (pin "1") (pinfunction "1_1") (pintype "passive"))
      (node (ref "C65") (pin "1") (pinfunction "1_1") (pintype "passive"))
      (node (ref "C66") (pin "1") (pinfunction "1_1") (pintype "passive"))
      (node (ref "C67") (pin "1") (pinfunction "1_1") (pintype "passive"))
      (node (ref "IC10") (pin "H1") (pinfunction "VREFDQ_H1") (pintype "power_in"))
      (node (ref "IC10") (pin "M8") (pinfunction "VREFCA_M8") (pintype "power_in"))
      (node (ref "IC11") (pin "H1") (pinfunction "VREFDQ_H1") (pintype "power_in"))
      (node (ref "IC11") (pin "M8") (pinfunction "VREFCA_M8") (pintype "power_in"))
      (node (ref "IC12") (pin "6") (pinfunction "REFOUT_6") (pintype "output"))
      (node (ref "IC8") (pin "H1") (pinfunction "VREFDQ_H1") (pintype "power_in"))
      (node (ref "IC8") (pin "M8") (pinfunction "VREFCA_M8") (pintype "power_in"))
      (node (ref "IC9") (pin "H1") (pinfunction "VREFDQ_H1") (pintype "power_in"))
      (node (ref "IC9") (pin "M8") (pinfunction "VREFCA_M8") (pintype "power_in"))
    )
    (net (code "120") (name "/DDR3_64_WE_N") (class "Default")
      (node (ref "IC10") (pin "L3") (pinfunction "~{WE}_L3") (pintype "input"))
      (node (ref "IC11") (pin "L3") (pinfunction "~{WE}_L3") (pintype "input"))
      (node (ref "IC8") (pin "L3") (pinfunction "~{WE}_L3") (pintype "input"))
      (node (ref "IC9") (pin "L3") (pinfunction "~{WE}_L3") (pintype "input"))
      (node (ref "R59") (pin "2") (pinfunction "2_2") (pintype "passive"))
    )
    (net (code "121") (name "/PGOOD") (class "Default")
      (node (ref "IC12") (pin "9") (pinfunction "PGOOD_9") (pintype "output"))
    )
    (net (code "122") (name "/REFIN") (class "Default")
      (node (ref "C339") (pin "2") (pinfunction "2_2") (pintype "passive"))
      (node (ref "IC12") (pin "1") (pinfunction "REFIN_1") (pintype "input"))
      (node (ref "R50") (pin "2") (pinfunction "2_2") (pintype "passive"))
      (node (ref "R51") (pin "2") (pinfunction "2_2") (pintype "passive"))
    )
    (net (code "124") (name "/VOSNS") (class "Default")
      (node (ref "C338") (pin "2") (pinfunction "2_2") (pintype "passive"))
      (node (ref "IC12") (pin "5") (pinfunction "VOSNS_5") (pintype "input"))
      (node (ref "R52") (pin "1") (pinfunction "1_1") (pintype "passive"))
    )
    (net (code "125") (name "/ZQ2") (class "Default")
      (node (ref "IC8") (pin "L8") (pinfunction "ZQ_L8") (pintype "input"))
      (node (ref "R54") (pin "2") (pinfunction "2_2") (pintype "passive"))
    )
    (net (code "127") (name "GND") (class "Default")
      (node (ref "C182") (pin "2") (pinfunction "2_2") (pintype "passive"))
      (node (ref "C23") (pin "2") (pinfunction "2_2") (pintype "passive"))
      (node (ref "C24") (pin "2") (pinfunction "2_2") (pintype "passive"))
      (node (ref "C25") (pin "2") (pinfunction "2_2") (pintype "passive"))
      (node (ref "C26") (pin "2") (pinfunction "2_2") (pintype "passive"))
      (node (ref "C27") (pin "2") (pinfunction "2_2") (pintype "passive"))
      (node (ref "C28") (pin "2") (pinfunction "2_2") (pintype "passive"))
      (node (ref "C29") (pin "2") (pinfunction "2_2") (pintype "passive"))
      (node (ref "C30") (pin "2") (pinfunction "2_2") (pintype "passive"))
      (node (ref "C31") (pin "2") (pinfunction "2_2") (pintype "passive"))
      (node (ref "C32") (pin "2") (pinfunction "2_2") (pintype "passive"))
      (node (ref "C33") (pin "2") (pinfunction "2_2") (pintype "passive"))
      (node (ref "C338") (pin "1") (pinfunction "1_1") (pintype "passive"))
      (node (ref "C339") (pin "1") (pinfunction "1_1") (pintype "passive"))
      (node (ref "C34") (pin "2") (pinfunction "2_2") (pintype "passive"))
      (node (ref "C340") (pin "2") (pinfunction "2_2") (pintype "passive"))
      (node (ref "C341") (pin "2") (pinfunction "2_2") (pintype "passive"))
      (node (ref "C342") (pin "2") (pinfunction "2_2") (pintype "passive"))
      (node (ref "C343") (pin "2") (pinfunction "2_2") (pintype "passive"))
      (node (ref "C344") (pin "2") (pinfunction "2_2") (pintype "passive"))
      (node (ref "C345") (pin "2") (pinfunction "2_2") (pintype "passive"))
      (node (ref "C346") (pin "2") (pinfunction "2_2") (pintype "passive"))
      (node (ref "C347") (pin "2") (pinfunction "2_2") (pintype "passive"))
      (node (ref "C348") (pin "2") (pinfunction "2_2") (pintype "passive"))
      (node (ref "C349") (pin "2") (pinfunction "2_2") (pintype "passive"))
      (node (ref "C35") (pin "2") (pinfunction "2_2") (pintype "passive"))
      (node (ref "C350") (pin "2") (pinfunction "2_2") (pintype "passive"))
      (node (ref "C36") (pin "2") (pinfunction "2_2") (pintype "passive"))
      (node (ref "C37") (pin "2") (pinfunction "2_2") (pintype "passive"))
      (node (ref "C38") (pin "2") (pinfunction "2_2") (pintype "passive"))
      (node (ref "C39") (pin "2") (pinfunction "2_2") (pintype "passive"))
      (node (ref "C40") (pin "2") (pinfunction "2_2") (pintype "passive"))
      (node (ref "C41") (pin "2") (pinfunction "2_2") (pintype "passive"))
      (node (ref "C42") (pin "2") (pinfunction "2_2") (pintype "passive"))
      (node (ref "C43") (pin "2") (pinfunction "2_2") (pintype "passive"))
      (node (ref "C44") (pin "2") (pinfunction "2_2") (pintype "passive"))
      (node (ref "C45") (pin "2") (pinfunction "2_2") (pintype "passive"))
      (node (ref "C455") (pin "1") (pinfunction "1_1") (pintype "passive"))
      (node (ref "C456") (pin "1") (pinfunction "1_1") (pintype "passive"))
      (node (ref "C47") (pin "2") (pinfunction "2_2") (pintype "passive"))
      (node (ref "C48") (pin "2") (pinfunction "2_2") (pintype "passive"))
      (node (ref "C49") (pin "2") (pinfunction "2_2") (pintype "passive"))
      (node (ref "C50") (pin "2") (pinfunction "2_2") (pintype "passive"))
      (node (ref "C51") (pin "2") (pinfunction "2_2") (pintype "passive"))
      (node (ref "C52") (pin "2") (pinfunction "2_2") (pintype "passive"))
      (node (ref "C53") (pin "2") (pinfunction "2_2") (pintype "passive"))
      (node (ref "C54") (pin "2") (pinfunction "2_2") (pintype "passive"))
      (node (ref "C55") (pin "2") (pinfunction "2_2") (pintype "passive"))
      (node (ref "C56") (pin "2") (pinfunction "2_2") (pintype "passive"))
      (node (ref "C57") (pin "2") (pinfunction "2_2") (pintype "passive"))
      (node (ref "C58") (pin "2") (pinfunction "2_2") (pintype "passive"))
      (node (ref "C59") (pin "2") (pinfunction "2_2") (pintype "passive"))
      (node (ref "C60") (pin "1") (pinfunction "1_1") (pintype "passive"))
      (node (ref "C61") (pin "2") (pinfunction "2_2") (pintype "passive"))
      (node (ref "C62") (pin "2") (pinfunction "2_2") (pintype "passive"))
      (node (ref "C63") (pin "1") (pinfunction "1_1") (pintype "passive"))
      (node (ref "C64") (pin "2") (pinfunction "2_2") (pintype "passive"))
      (node (ref "C65") (pin "2") (pinfunction "2_2") (pintype "passive"))
      (node (ref "C66") (pin "2") (pinfunction "2_2") (pintype "passive"))
      (node (ref "C67") (pin "2") (pinfunction "2_2") (pintype "passive"))
      (node (ref "C68") (pin "2") (pinfunction "2_2") (pintype "passive"))
      (node (ref "C69") (pin "2") (pinfunction "2_2") (pintype "passive"))
      (node (ref "C70") (pin "2") (pinfunction "2_2") (pintype "passive"))
      (node (ref "C71") (pin "2") (pinfunction "2_2") (pintype "passive"))
      (node (ref "C72") (pin "2") (pinfunction "2_2") (pintype "passive"))
      (node (ref "C73") (pin "2") (pinfunction "2_2") (pintype "passive"))
      (node (ref "C74") (pin "2") (pinfunction "2_2") (pintype "passive"))
      (node (ref "C75") (pin "2") (pinfunction "2_2") (pintype "passive"))
      (node (ref "C76") (pin "2") (pinfunction "2_2") (pintype "passive"))
      (node (ref "C77") (pin "2") (pinfunction "2_2") (pintype "passive"))
      (node (ref "C78") (pin "2") (pinfunction "2_2") (pintype "passive"))
      (node (ref "C79") (pin "2") (pinfunction "2_2") (pintype "passive"))
      (node (ref "C80") (pin "2") (pinfunction "2_2") (pintype "passive"))
      (node (ref "C81") (pin "2") (pinfunction "2_2") (pintype "passive"))
      (node (ref "C82") (pin "2") (pinfunction "2_2") (pintype "passive"))
      (node (ref "C83") (pin "2") (pinfunction "2_2") (pintype "passive"))
      (node (ref "C84") (pin "2") (pinfunction "2_2") (pintype "passive"))
      (node (ref "C85") (pin "2") (pinfunction "2_2") (pintype "passive"))
      (node (ref "C86") (pin "2") (pinfunction "2_2") (pintype "passive"))
      (node (ref "C87") (pin "2") (pinfunction "2_2") (pintype "passive"))
      (node (ref "C88") (pin "2") (pinfunction "2_2") (pintype "passive"))
      (node (ref "C89") (pin "2") (pinfunction "2_2") (pintype "passive"))
      (node (ref "C90") (pin "2") (pinfunction "2_2") (pintype "passive"))
      (node (ref "C91") (pin "1") (pinfunction "1_1") (pintype "passive"))
      (node (ref "IC10") (pin "A9") (pinfunction "VSS_A9") (pintype "power_in"))
      (node (ref "IC10") (pin "B1") (pinfunction "VSSQ_B1") (pintype "power_in"))
      (node (ref "IC10") (pin "B3") (pinfunction "VSS_B3") (pintype "power_in"))
      (node (ref "IC10") (pin "B9") (pinfunction "VSSQ_B9") (pintype "power_in"))
      (node (ref "IC10") (pin "D1") (pinfunction "VSSQ_D1") (pintype "power_in"))
      (node (ref "IC10") (pin "D8") (pinfunction "VSSQ_D8") (pintype "power_in"))
      (node (ref "IC10") (pin "E1") (pinfunction "VSS_E1") (pintype "power_in"))
      (node (ref "IC10") (pin "E2") (pinfunction "VSSQ_E2") (pintype "power_in"))
      (node (ref "IC10") (pin "E8") (pinfunction "VSSQ_E8") (pintype "power_in"))
      (node (ref "IC10") (pin "F9") (pinfunction "VSSQ_F9") (pintype "power_in"))
      (node (ref "IC10") (pin "G1") (pinfunction "VSSQ_G1") (pintype "power_in"))
      (node (ref "IC10") (pin "G8") (pinfunction "VSS_G8") (pintype "power_in"))
      (node (ref "IC10") (pin "G9") (pinfunction "VSSQ_G9") (pintype "power_in"))
      (node (ref "IC10") (pin "J2") (pinfunction "VSS_J2") (pintype "power_in"))
      (node (ref "IC10") (pin "J8") (pinfunction "VSS_J8") (pintype "power_in"))
      (node (ref "IC10") (pin "M1") (pinfunction "VSS_M1") (pintype "power_in"))
      (node (ref "IC10") (pin "M9") (pinfunction "VSS_M9") (pintype "power_in"))
      (node (ref "IC10") (pin "P1") (pinfunction "VSS_P1") (pintype "power_in"))
      (node (ref "IC10") (pin "P9") (pinfunction "VSS_P9") (pintype "power_in"))
      (node (ref "IC10") (pin "T1") (pinfunction "VSS_T1") (pintype "power_in"))
      (node (ref "IC10") (pin "T9") (pinfunction "VSS_T9") (pintype "power_in"))
      (node (ref "IC11") (pin "A9") (pinfunction "VSS_A9") (pintype "power_in"))
      (node (ref "IC11") (pin "B1") (pinfunction "VSSQ_B1") (pintype "power_in"))
      (node (ref "IC11") (pin "B3") (pinfunction "VSS_B3") (pintype "power_in"))
      (node (ref "IC11") (pin "B9") (pinfunction "VSSQ_B9") (pintype "power_in"))
      (node (ref "IC11") (pin "D1") (pinfunction "VSSQ_D1") (pintype "power_in"))
      (node (ref "IC11") (pin "D8") (pinfunction "VSSQ_D8") (pintype "power_in"))
      (node (ref "IC11") (pin "E1") (pinfunction "VSS_E1") (pintype "power_in"))
      (node (ref "IC11") (pin "E2") (pinfunction "VSSQ_E2") (pintype "power_in"))
      (node (ref "IC11") (pin "E8") (pinfunction "VSSQ_E8") (pintype "power_in"))
      (node (ref "IC11") (pin "F9") (pinfunction "VSSQ_F9") (pintype "power_in"))
      (node (ref "IC11") (pin "G1") (pinfunction "VSSQ_G1") (pintype "power_in"))
      (node (ref "IC11") (pin "G8") (pinfunction "VSS_G8") (pintype "power_in"))
      (node (ref "IC11") (pin "G9") (pinfunction "VSSQ_G9") (pintype "power_in"))
      (node (ref "IC11") (pin "J2") (pinfunction "VSS_J2") (pintype "power_in"))
      (node (ref "IC11") (pin "J8") (pinfunction "VSS_J8") (pintype "power_in"))
      (node (ref "IC11") (pin "M1") (pinfunction "VSS_M1") (pintype "power_in"))
      (node (ref "IC11") (pin "M9") (pinfunction "VSS_M9") (pintype "power_in"))
      (node (ref "IC11") (pin "P1") (pinfunction "VSS_P1") (pintype "power_in"))
      (node (ref "IC11") (pin "P9") (pinfunction "VSS_P9") (pintype "power_in"))
      (node (ref "IC11") (pin "T1") (pinfunction "VSS_T1") (pintype "power_in"))
      (node (ref "IC11") (pin "T9") (pinfunction "VSS_T9") (pintype "power_in"))
      (node (ref "IC12") (pin "11") (pinfunction "EP_11") (pintype "power_in"))
      (node (ref "IC12") (pin "4") (pinfunction "PGND_4") (pintype "power_in"))
      (node (ref "IC12") (pin "8") (pinfunction "GND_8") (pintype "power_in"))
      (node (ref "IC8") (pin "A9") (pinfunction "VSS_A9") (pintype "power_in"))
      (node (ref "IC8") (pin "B1") (pinfunction "VSSQ_B1") (pintype "power_in"))
      (node (ref "IC8") (pin "B3") (pinfunction "VSS_B3") (pintype "power_in"))
      (node (ref "IC8") (pin "B9") (pinfunction "VSSQ_B9") (pintype "power_in"))
      (node (ref "IC8") (pin "D1") (pinfunction "VSSQ_D1") (pintype "power_in"))
      (node (ref "IC8") (pin "D8") (pinfunction "VSSQ_D8") (pintype "power_in"))
      (node (ref "IC8") (pin "E1") (pinfunction "VSS_E1") (pintype "power_in"))
      (node (ref "IC8") (pin "E2") (pinfunction "VSSQ_E2") (pintype "power_in"))
      (node (ref "IC8") (pin "E8") (pinfunction "VSSQ_E8") (pintype "power_in"))
      (node (ref "IC8") (pin "F9") (pinfunction "VSSQ_F9") (pintype "power_in"))
      (node (ref "IC8") (pin "G1") (pinfunction "VSSQ_G1") (pintype "power_in"))
      (node (ref "IC8") (pin "G8") (pinfunction "VSS_G8") (pintype "power_in"))
      (node (ref "IC8") (pin "G9") (pinfunction "VSSQ_G9") (pintype "power_in"))
      (node (ref "IC8") (pin "J2") (pinfunction "VSS_J2") (pintype "power_in"))
      (node (ref "IC8") (pin "J8") (pinfunction "VSS_J8") (pintype "power_in"))
      (node (ref "IC8") (pin "M1") (pinfunction "VSS_M1") (pintype "power_in"))
      (node (ref "IC8") (pin "M9") (pinfunction "VSS_M9") (pintype "power_in"))
      (node (ref "IC8") (pin "P1") (pinfunction "VSS_P1") (pintype "power_in"))
      (node (ref "IC8") (pin "P9") (pinfunction "VSS_P9") (pintype "power_in"))
      (node (ref "IC8") (pin "T1") (pinfunction "VSS_T1") (pintype "power_in"))
      (node (ref "IC8") (pin "T9") (pinfunction "VSS_T9") (pintype "power_in"))
      (node (ref "IC9") (pin "A9") (pinfunction "VSS_A9") (pintype "power_in"))
      (node (ref "IC9") (pin "B1") (pinfunction "VSSQ_B1") (pintype "power_in"))
      (node (ref "IC9") (pin "B3") (pinfunction "VSS_B3") (pintype "power_in"))
      (node (ref "IC9") (pin "B9") (pinfunction "VSSQ_B9") (pintype "power_in"))
      (node (ref "IC9") (pin "D1") (pinfunction "VSSQ_D1") (pintype "power_in"))
      (node (ref "IC9") (pin "D8") (pinfunction "VSSQ_D8") (pintype "power_in"))
      (node (ref "IC9") (pin "E1") (pinfunction "VSS_E1") (pintype "power_in"))
      (node (ref "IC9") (pin "E2") (pinfunction "VSSQ_E2") (pintype "power_in"))
      (node (ref "IC9") (pin "E8") (pinfunction "VSSQ_E8") (pintype "power_in"))
      (node (ref "IC9") (pin "F9") (pinfunction "VSSQ_F9") (pintype "power_in"))
      (node (ref "IC9") (pin "G1") (pinfunction "VSSQ_G1") (pintype "power_in"))
      (node (ref "IC9") (pin "G8") (pinfunction "VSS_G8") (pintype "power_in"))
      (node (ref "IC9") (pin "G9") (pinfunction "VSSQ_G9") (pintype "power_in"))
      (node (ref "IC9") (pin "J2") (pinfunction "VSS_J2") (pintype "power_in"))
      (node (ref "IC9") (pin "J8") (pinfunction "VSS_J8") (pintype "power_in"))
      (node (ref "IC9") (pin "M1") (pinfunction "VSS_M1") (pintype "power_in"))
      (node (ref "IC9") (pin "M9") (pinfunction "VSS_M9") (pintype "power_in"))
      (node (ref "IC9") (pin "P1") (pinfunction "VSS_P1") (pintype "power_in"))
      (node (ref "IC9") (pin "P9") (pinfunction "VSS_P9") (pintype "power_in"))
      (node (ref "IC9") (pin "T1") (pinfunction "VSS_T1") (pintype "power_in"))
      (node (ref "IC9") (pin "T9") (pinfunction "VSS_T9") (pintype "power_in"))
      (node (ref "R51") (pin "1") (pinfunction "1_1") (pintype "passive"))
      (node (ref "R53") (pin "1") (pinfunction "1_1") (pintype "passive"))
      (node (ref "R54") (pin "1") (pinfunction "1_1") (pintype "passive"))
      (node (ref "R80") (pin "1") (pinfunction "1_1") (pintype "passive"))
      (node (ref "R81") (pin "1") (pinfunction "1_1") (pintype "passive"))
      (node (ref "R82") (pin "1") (pinfunction "1_1") (pintype "passive"))
    )
    (net (code "128") (name "Net-(IC9-ZQ)") (class "Default")
      (node (ref "IC9") (pin "L8") (pinfunction "ZQ_L8") (pintype "input"))
      (node (ref "R53") (pin "2") (pinfunction "2_2") (pintype "passive"))
    )
    (net (code "129") (name "Net-(IC10-ZQ)") (class "Default")
      (node (ref "IC10") (pin "L8") (pinfunction "ZQ_L8") (pintype "input"))
      (node (ref "R81") (pin "2") (pinfunction "2_2") (pintype "passive"))
    )
    (net (code "130") (name "Net-(IC11-ZQ)") (class "Default")
      (node (ref "IC11") (pin "L8") (pinfunction "ZQ_L8") (pintype "input"))
      (node (ref "R82") (pin "2") (pinfunction "2_2") (pintype "passive"))
    )
    (net (code "131") (name "P1V5") (class "Default")
      (node (ref "C182") (pin "1") (pinfunction "1_1") (pintype "passive"))
      (node (ref "C341") (pin "1") (pinfunction "1_1") (pintype "passive"))
      (node (ref "C342") (pin "1") (pinfunction "1_1") (pintype "passive"))
      (node (ref "C343") (pin "1") (pinfunction "1_1") (pintype "passive"))
      (node (ref "C344") (pin "1") (pinfunction "1_1") (pintype "passive"))
      (node (ref "C346") (pin "1") (pinfunction "1_1") (pintype "passive"))
      (node (ref "C347") (pin "1") (pinfunction "1_1") (pintype "passive"))
      (node (ref "C348") (pin "1") (pinfunction "1_1") (pintype "passive"))
      (node (ref "C349") (pin "1") (pinfunction "1_1") (pintype "passive"))
      (node (ref "C35") (pin "1") (pinfunction "1_1") (pintype "passive"))
      (node (ref "C350") (pin "1") (pinfunction "1_1") (pintype "passive"))
      (node (ref "C36") (pin "1") (pinfunction "1_1") (pintype "passive"))
      (node (ref "C37") (pin "1") (pinfunction "1_1") (pintype "passive"))
      (node (ref "C38") (pin "1") (pinfunction "1_1") (pintype "passive"))
      (node (ref "C39") (pin "1") (pinfunction "1_1") (pintype "passive"))
      (node (ref "C40") (pin "1") (pinfunction "1_1") (pintype "passive"))
      (node (ref "C41") (pin "1") (pinfunction "1_1") (pintype "passive"))
      (node (ref "C42") (pin "1") (pinfunction "1_1") (pintype "passive"))
      (node (ref "C43") (pin "1") (pinfunction "1_1") (pintype "passive"))
      (node (ref "C44") (pin "1") (pinfunction "1_1") (pintype "passive"))
      (node (ref "C45") (pin "1") (pinfunction "1_1") (pintype "passive"))
      (node (ref "C47") (pin "1") (pinfunction "1_1") (pintype "passive"))
      (node (ref "C48") (pin "1") (pinfunction "1_1") (pintype "passive"))
      (node (ref "C49") (pin "1") (pinfunction "1_1") (pintype "passive"))
      (node (ref "C50") (pin "1") (pinfunction "1_1") (pintype "passive"))
      (node (ref "C51") (pin "1") (pinfunction "1_1") (pintype "passive"))
      (node (ref "C52") (pin "1") (pinfunction "1_1") (pintype "passive"))
      (node (ref "C53") (pin "1") (pinfunction "1_1") (pintype "passive"))
      (node (ref "C54") (pin "1") (pinfunction "1_1") (pintype "passive"))
      (node (ref "C55") (pin "1") (pinfunction "1_1") (pintype "passive"))
      (node (ref "C56") (pin "1") (pinfunction "1_1") (pintype "passive"))
      (node (ref "C57") (pin "1") (pinfunction "1_1") (pintype "passive"))
      (node (ref "C60") (pin "2") (pinfunction "2_2") (pintype "passive"))
      (node (ref "C68") (pin "1") (pinfunction "1_1") (pintype "passive"))
      (node (ref "C69") (pin "1") (pinfunction "1_1") (pintype "passive"))
      (node (ref "C70") (pin "1") (pinfunction "1_1") (pintype "passive"))
      (node (ref "C71") (pin "1") (pinfunction "1_1") (pintype "passive"))
      (node (ref "C72") (pin "1") (pinfunction "1_1") (pintype "passive"))
      (node (ref "C73") (pin "1") (pinfunction "1_1") (pintype "passive"))
      (node (ref "C74") (pin "1") (pinfunction "1_1") (pintype "passive"))
      (node (ref "C75") (pin "1") (pinfunction "1_1") (pintype "passive"))
      (node (ref "C76") (pin "1") (pinfunction "1_1") (pintype "passive"))
      (node (ref "C77") (pin "1") (pinfunction "1_1") (pintype "passive"))
      (node (ref "C78") (pin "1") (pinfunction "1_1") (pintype "passive"))
      (node (ref "C79") (pin "1") (pinfunction "1_1") (pintype "passive"))
      (node (ref "C80") (pin "1") (pinfunction "1_1") (pintype "passive"))
      (node (ref "C81") (pin "1") (pinfunction "1_1") (pintype "passive"))
      (node (ref "C82") (pin "1") (pinfunction "1_1") (pintype "passive"))
      (node (ref "C83") (pin "1") (pinfunction "1_1") (pintype "passive"))
      (node (ref "C84") (pin "1") (pinfunction "1_1") (pintype "passive"))
      (node (ref "C85") (pin "1") (pinfunction "1_1") (pintype "passive"))
      (node (ref "C86") (pin "1") (pinfunction "1_1") (pintype "passive"))
      (node (ref "C87") (pin "1") (pinfunction "1_1") (pintype "passive"))
      (node (ref "C88") (pin "1") (pinfunction "1_1") (pintype "passive"))
      (node (ref "C89") (pin "1") (pinfunction "1_1") (pintype "passive"))
      (node (ref "C90") (pin "1") (pinfunction "1_1") (pintype "passive"))
      (node (ref "C91") (pin "2") (pinfunction "2_2") (pintype "passive"))
      (node (ref "IC10") (pin "A1") (pinfunction "VDDQ_A1") (pintype "power_in"))
      (node (ref "IC10") (pin "A8") (pinfunction "VDDQ_A8") (pintype "power_in"))
      (node (ref "IC10") (pin "B2") (pinfunction "VDD_B2") (pintype "power_in"))
      (node (ref "IC10") (pin "C1") (pinfunction "VDDQ_C1") (pintype "power_in"))
      (node (ref "IC10") (pin "C9") (pinfunction "VDDQ_C9") (pintype "power_in"))
      (node (ref "IC10") (pin "D2") (pinfunction "VDDQ_D2") (pintype "power_in"))
      (node (ref "IC10") (pin "D9") (pinfunction "VDD_D9") (pintype "power_in"))
      (node (ref "IC10") (pin "E9") (pinfunction "VDDQ_E9") (pintype "power_in"))
      (node (ref "IC10") (pin "F1") (pinfunction "VDDQ_F1") (pintype "power_in"))
      (node (ref "IC10") (pin "G7") (pinfunction "VDD_G7") (pintype "power_in"))
      (node (ref "IC10") (pin "H2") (pinfunction "VDDQ_H2") (pintype "power_in"))
      (node (ref "IC10") (pin "H9") (pinfunction "VDDQ_H9") (pintype "power_in"))
      (node (ref "IC10") (pin "K2") (pinfunction "VDD_K2") (pintype "power_in"))
      (node (ref "IC10") (pin "K8") (pinfunction "VDD_K8") (pintype "power_in"))
      (node (ref "IC10") (pin "N1") (pinfunction "VDD_N1") (pintype "power_in"))
      (node (ref "IC10") (pin "N9") (pinfunction "VDD_N9") (pintype "power_in"))
      (node (ref "IC10") (pin "R1") (pinfunction "VDD_R1") (pintype "power_in"))
      (node (ref "IC10") (pin "R9") (pinfunction "VDD_R9") (pintype "power_in"))
      (node (ref "IC11") (pin "A1") (pinfunction "VDDQ_A1") (pintype "power_in"))
      (node (ref "IC11") (pin "A8") (pinfunction "VDDQ_A8") (pintype "power_in"))
      (node (ref "IC11") (pin "B2") (pinfunction "VDD_B2") (pintype "power_in"))
      (node (ref "IC11") (pin "C1") (pinfunction "VDDQ_C1") (pintype "power_in"))
      (node (ref "IC11") (pin "C9") (pinfunction "VDDQ_C9") (pintype "power_in"))
      (node (ref "IC11") (pin "D2") (pinfunction "VDDQ_D2") (pintype "power_in"))
      (node (ref "IC11") (pin "D9") (pinfunction "VDD_D9") (pintype "power_in"))
      (node (ref "IC11") (pin "E9") (pinfunction "VDDQ_E9") (pintype "power_in"))
      (node (ref "IC11") (pin "F1") (pinfunction "VDDQ_F1") (pintype "power_in"))
      (node (ref "IC11") (pin "G7") (pinfunction "VDD_G7") (pintype "power_in"))
      (node (ref "IC11") (pin "H2") (pinfunction "VDDQ_H2") (pintype "power_in"))
      (node (ref "IC11") (pin "H9") (pinfunction "VDDQ_H9") (pintype "power_in"))
      (node (ref "IC11") (pin "K2") (pinfunction "VDD_K2") (pintype "power_in"))
      (node (ref "IC11") (pin "K8") (pinfunction "VDD_K8") (pintype "power_in"))
      (node (ref "IC11") (pin "N1") (pinfunction "VDD_N1") (pintype "power_in"))
      (node (ref "IC11") (pin "N9") (pinfunction "VDD_N9") (pintype "power_in"))
      (node (ref "IC11") (pin "R1") (pinfunction "VDD_R1") (pintype "power_in"))
      (node (ref "IC11") (pin "R9") (pinfunction "VDD_R9") (pintype "power_in"))
      (node (ref "IC12") (pin "2") (pinfunction "VLDOIN_2") (pintype "input"))
      (node (ref "IC8") (pin "A1") (pinfunction "VDDQ_A1") (pintype "power_in"))
      (node (ref "IC8") (pin "A8") (pinfunction "VDDQ_A8") (pintype "power_in"))
      (node (ref "IC8") (pin "B2") (pinfunction "VDD_B2") (pintype "power_in"))
      (node (ref "IC8") (pin "C1") (pinfunction "VDDQ_C1") (pintype "power_in"))
      (node (ref "IC8") (pin "C9") (pinfunction "VDDQ_C9") (pintype "power_in"))
      (node (ref "IC8") (pin "D2") (pinfunction "VDDQ_D2") (pintype "power_in"))
      (node (ref "IC8") (pin "D9") (pinfunction "VDD_D9") (pintype "power_in"))
      (node (ref "IC8") (pin "E9") (pinfunction "VDDQ_E9") (pintype "power_in"))
      (node (ref "IC8") (pin "F1") (pinfunction "VDDQ_F1") (pintype "power_in"))
      (node (ref "IC8") (pin "G7") (pinfunction "VDD_G7") (pintype "power_in"))
      (node (ref "IC8") (pin "H2") (pinfunction "VDDQ_H2") (pintype "power_in"))
      (node (ref "IC8") (pin "H9") (pinfunction "VDDQ_H9") (pintype "power_in"))
      (node (ref "IC8") (pin "K2") (pinfunction "VDD_K2") (pintype "power_in"))
      (node (ref "IC8") (pin "K8") (pinfunction "VDD_K8") (pintype "power_in"))
      (node (ref "IC8") (pin "N1") (pinfunction "VDD_N1") (pintype "power_in"))
      (node (ref "IC8") (pin "N9") (pinfunction "VDD_N9") (pintype "power_in"))
      (node (ref "IC8") (pin "R1") (pinfunction "VDD_R1") (pintype "power_in"))
      (node (ref "IC8") (pin "R9") (pinfunction "VDD_R9") (pintype "power_in"))
      (node (ref "IC9") (pin "A1") (pinfunction "VDDQ_A1") (pintype "power_in"))
      (node (ref "IC9") (pin "A8") (pinfunction "VDDQ_A8") (pintype "power_in"))
      (node (ref "IC9") (pin "B2") (pinfunction "VDD_B2") (pintype "power_in"))
      (node (ref "IC9") (pin "C1") (pinfunction "VDDQ_C1") (pintype "power_in"))
      (node (ref "IC9") (pin "C9") (pinfunction "VDDQ_C9") (pintype "power_in"))
      (node (ref "IC9") (pin "D2") (pinfunction "VDDQ_D2") (pintype "power_in"))
      (node (ref "IC9") (pin "D9") (pinfunction "VDD_D9") (pintype "power_in"))
      (node (ref "IC9") (pin "E9") (pinfunction "VDDQ_E9") (pintype "power_in"))
      (node (ref "IC9") (pin "F1") (pinfunction "VDDQ_F1") (pintype "power_in"))
      (node (ref "IC9") (pin "G7") (pinfunction "VDD_G7") (pintype "power_in"))
      (node (ref "IC9") (pin "H2") (pinfunction "VDDQ_H2") (pintype "power_in"))
      (node (ref "IC9") (pin "H9") (pinfunction "VDDQ_H9") (pintype "power_in"))
      (node (ref "IC9") (pin "K2") (pinfunction "VDD_K2") (pintype "power_in"))
      (node (ref "IC9") (pin "K8") (pinfunction "VDD_K8") (pintype "power_in"))
      (node (ref "IC9") (pin "N1") (pinfunction "VDD_N1") (pintype "power_in"))
      (node (ref "IC9") (pin "N9") (pinfunction "VDD_N9") (pintype "power_in"))
      (node (ref "IC9") (pin "R1") (pinfunction "VDD_R1") (pintype "power_in"))
      (node (ref "IC9") (pin "R9") (pinfunction "VDD_R9") (pintype "power_in"))
      (node (ref "R50") (pin "1") (pinfunction "1_1") (pintype "passive"))
    )
    (net (code "132") (name "P3V3") (class "Default")
      (node (ref "C345") (pin "1") (pinfunction "1_1") (pintype "passive"))
      (node (ref "IC12") (pin "10") (pinfunction "VIN_10") (pintype "input"))
      (node (ref "IC12") (pin "7") (pinfunction "EN_7") (pintype "input"))
    )
    (net (code "133") (name "VTT64") (class "Default")
      (node (ref "C23") (pin "1") (pinfunction "1_1") (pintype "passive"))
      (node (ref "C24") (pin "1") (pinfunction "1_1") (pintype "passive"))
      (node (ref "C25") (pin "1") (pinfunction "1_1") (pintype "passive"))
      (node (ref "C26") (pin "1") (pinfunction "1_1") (pintype "passive"))
      (node (ref "C27") (pin "1") (pinfunction "1_1") (pintype "passive"))
      (node (ref "C28") (pin "1") (pinfunction "1_1") (pintype "passive"))
      (node (ref "C29") (pin "1") (pinfunction "1_1") (pintype "passive"))
      (node (ref "C30") (pin "1") (pinfunction "1_1") (pintype "passive"))
      (node (ref "C31") (pin "1") (pinfunction "1_1") (pintype "passive"))
      (node (ref "C32") (pin "1") (pinfunction "1_1") (pintype "passive"))
      (node (ref "C33") (pin "1") (pinfunction "1_1") (pintype "passive"))
      (node (ref "C34") (pin "1") (pinfunction "1_1") (pintype "passive"))
      (node (ref "C340") (pin "1") (pinfunction "1_1") (pintype "passive"))
      (node (ref "C455") (pin "2") (pinfunction "2_2") (pintype "passive"))
      (node (ref "C456") (pin "2") (pinfunction "2_2") (pintype "passive"))
      (node (ref "IC12") (pin "3") (pinfunction "VO_3") (pintype "power_in"))
      (node (ref "R52") (pin "2") (pinfunction "2_2") (pintype "passive"))
      (node (ref "R55") (pin "1") (pinfunction "1_1") (pintype "passive"))
      (node (ref "R56") (pin "1") (pinfunction "1_1") (pintype "passive"))
      (node (ref "R57") (pin "1") (pinfunction "1_1") (pintype "passive"))
      (node (ref "R58") (pin "1") (pinfunction "1_1") (pintype "passive"))
      (node (ref "R59") (pin "1") (pinfunction "1_1") (pintype "passive"))
      (node (ref "R60") (pin "1") (pinfunction "1_1") (pintype "passive"))
      (node (ref "R61") (pin "1") (pinfunction "1_1") (pintype "passive"))
      (node (ref "R62") (pin "1") (pinfunction "1_1") (pintype "passive"))
      (node (ref "R63") (pin "1") (pinfunction "1_1") (pintype "passive"))
      (node (ref "R64") (pin "1") (pinfunction "1_1") (pintype "passive"))
      (node (ref "R65") (pin "1") (pinfunction "1_1") (pintype "passive"))
      (node (ref "R66") (pin "1") (pinfunction "1_1") (pintype "passive"))
      (node (ref "R67") (pin "1") (pinfunction "1_1") (pintype "passive"))
      (node (ref "R68") (pin "1") (pinfunction "1_1") (pintype "passive"))
      (node (ref "R69") (pin "1") (pinfunction "1_1") (pintype "passive"))
      (node (ref "R70") (pin "1") (pinfunction "1_1") (pintype "passive"))
      (node (ref "R71") (pin "1") (pinfunction "1_1") (pintype "passive"))
      (node (ref "R72") (pin "1") (pinfunction "1_1") (pintype "passive"))
      (node (ref "R73") (pin "1") (pinfunction "1_1") (pintype "passive"))
      (node (ref "R74") (pin "1") (pinfunction "1_1") (pintype "passive"))
      (node (ref "R75") (pin "1") (pinfunction "1_1") (pintype "passive"))
      (node (ref "R76") (pin "1") (pinfunction "1_1") (pintype "passive"))
      (node (ref "R77") (pin "1") (pinfunction "1_1") (pintype "passive"))
      (node (ref "R78") (pin "1") (pinfunction "1_1") (pintype "passive"))
      (node (ref "R79") (pin "1") (pinfunction "1_1") (pintype "passive"))
      (node (ref "R83") (pin "1") (pinfunction "1_1") (pintype "passive"))
    )
    (net (code "134") (name "unconnected-(IC8-NC-PadJ1)") (class "Default")
      (node (ref "IC8") (pin "J1") (pinfunction "NC_J1") (pintype "passive"))
    )
    (net (code "135") (name "unconnected-(IC8-NC-PadJ9)") (class "Default")
      (node (ref "IC8") (pin "J9") (pinfunction "NC_J9") (pintype "passive"))
    )
    (net (code "136") (name "unconnected-(IC8-NC-PadL1)") (class "Default")
      (node (ref "IC8") (pin "L1") (pinfunction "NC_L1") (pintype "passive"))
    )
    (net (code "137") (name "unconnected-(IC8-NC-PadL9)") (class "Default")
      (node (ref "IC8") (pin "L9") (pinfunction "NC_L9") (pintype "passive"))
    )
    (net (code "138") (name "unconnected-(IC8-NC-PadM7)") (class "Default")
      (node (ref "IC8") (pin "M7") (pinfunction "NC_M7") (pintype "passive"))
    )
    (net (code "139") (name "unconnected-(IC9-NC-PadJ1)") (class "Default")
      (node (ref "IC9") (pin "J1") (pinfunction "NC_J1") (pintype "passive"))
    )
    (net (code "140") (name "unconnected-(IC9-NC-PadJ9)") (class "Default")
      (node (ref "IC9") (pin "J9") (pinfunction "NC_J9") (pintype "passive"))
    )
    (net (code "141") (name "unconnected-(IC9-NC-PadL1)") (class "Default")
      (node (ref "IC9") (pin "L1") (pinfunction "NC_L1") (pintype "passive"))
    )
    (net (code "142") (name "unconnected-(IC9-NC-PadL9)") (class "Default")
      (node (ref "IC9") (pin "L9") (pinfunction "NC_L9") (pintype "passive"))
    )
    (net (code "143") (name "unconnected-(IC9-NC-PadM7)") (class "Default")
      (node (ref "IC9") (pin "M7") (pinfunction "NC_M7") (pintype "passive"))
    )
    (net (code "144") (name "unconnected-(IC10-NC-PadJ1)") (class "Default")
      (node (ref "IC10") (pin "J1") (pinfunction "NC_J1") (pintype "passive"))
    )
    (net (code "145") (name "unconnected-(IC10-NC-PadJ9)") (class "Default")
      (node (ref "IC10") (pin "J9") (pinfunction "NC_J9") (pintype "passive"))
    )
    (net (code "146") (name "unconnected-(IC10-NC-PadL1)") (class "Default")
      (node (ref "IC10") (pin "L1") (pinfunction "NC_L1") (pintype "passive"))
    )
    (net (code "147") (name "unconnected-(IC10-NC-PadL9)") (class "Default")
      (node (ref "IC10") (pin "L9") (pinfunction "NC_L9") (pintype "passive"))
    )
    (net (code "148") (name "unconnected-(IC10-NC-PadM7)") (class "Default")
      (node (ref "IC10") (pin "M7") (pinfunction "NC_M7") (pintype "passive"))
    )
    (net (code "149") (name "unconnected-(IC11-NC-PadJ1)") (class "Default")
      (node (ref "IC11") (pin "J1") (pinfunction "NC_J1") (pintype "passive"))
    )
    (net (code "150") (name "unconnected-(IC11-NC-PadJ9)") (class "Default")
      (node (ref "IC11") (pin "J9") (pinfunction "NC_J9") (pintype "passive"))
    )
    (net (code "151") (name "unconnected-(IC11-NC-PadL1)") (class "Default")
      (node (ref "IC11") (pin "L1") (pinfunction "NC_L1") (pintype "passive"))
    )
    (net (code "152") (name "unconnected-(IC11-NC-PadL9)") (class "Default")
      (node (ref "IC11") (pin "L9") (pinfunction "NC_L9") (pintype "passive"))
    )
    (net (code "153") (name "unconnected-(IC11-NC-PadM7)") (class "Default")
      (node (ref "IC11") (pin "M7") (pinfunction "NC_M7") (pintype "passive"))
    )
  )
)
